# Solderable_Breadboard_Large.net
KiCad netlist of a schematic drawn in EAGLE
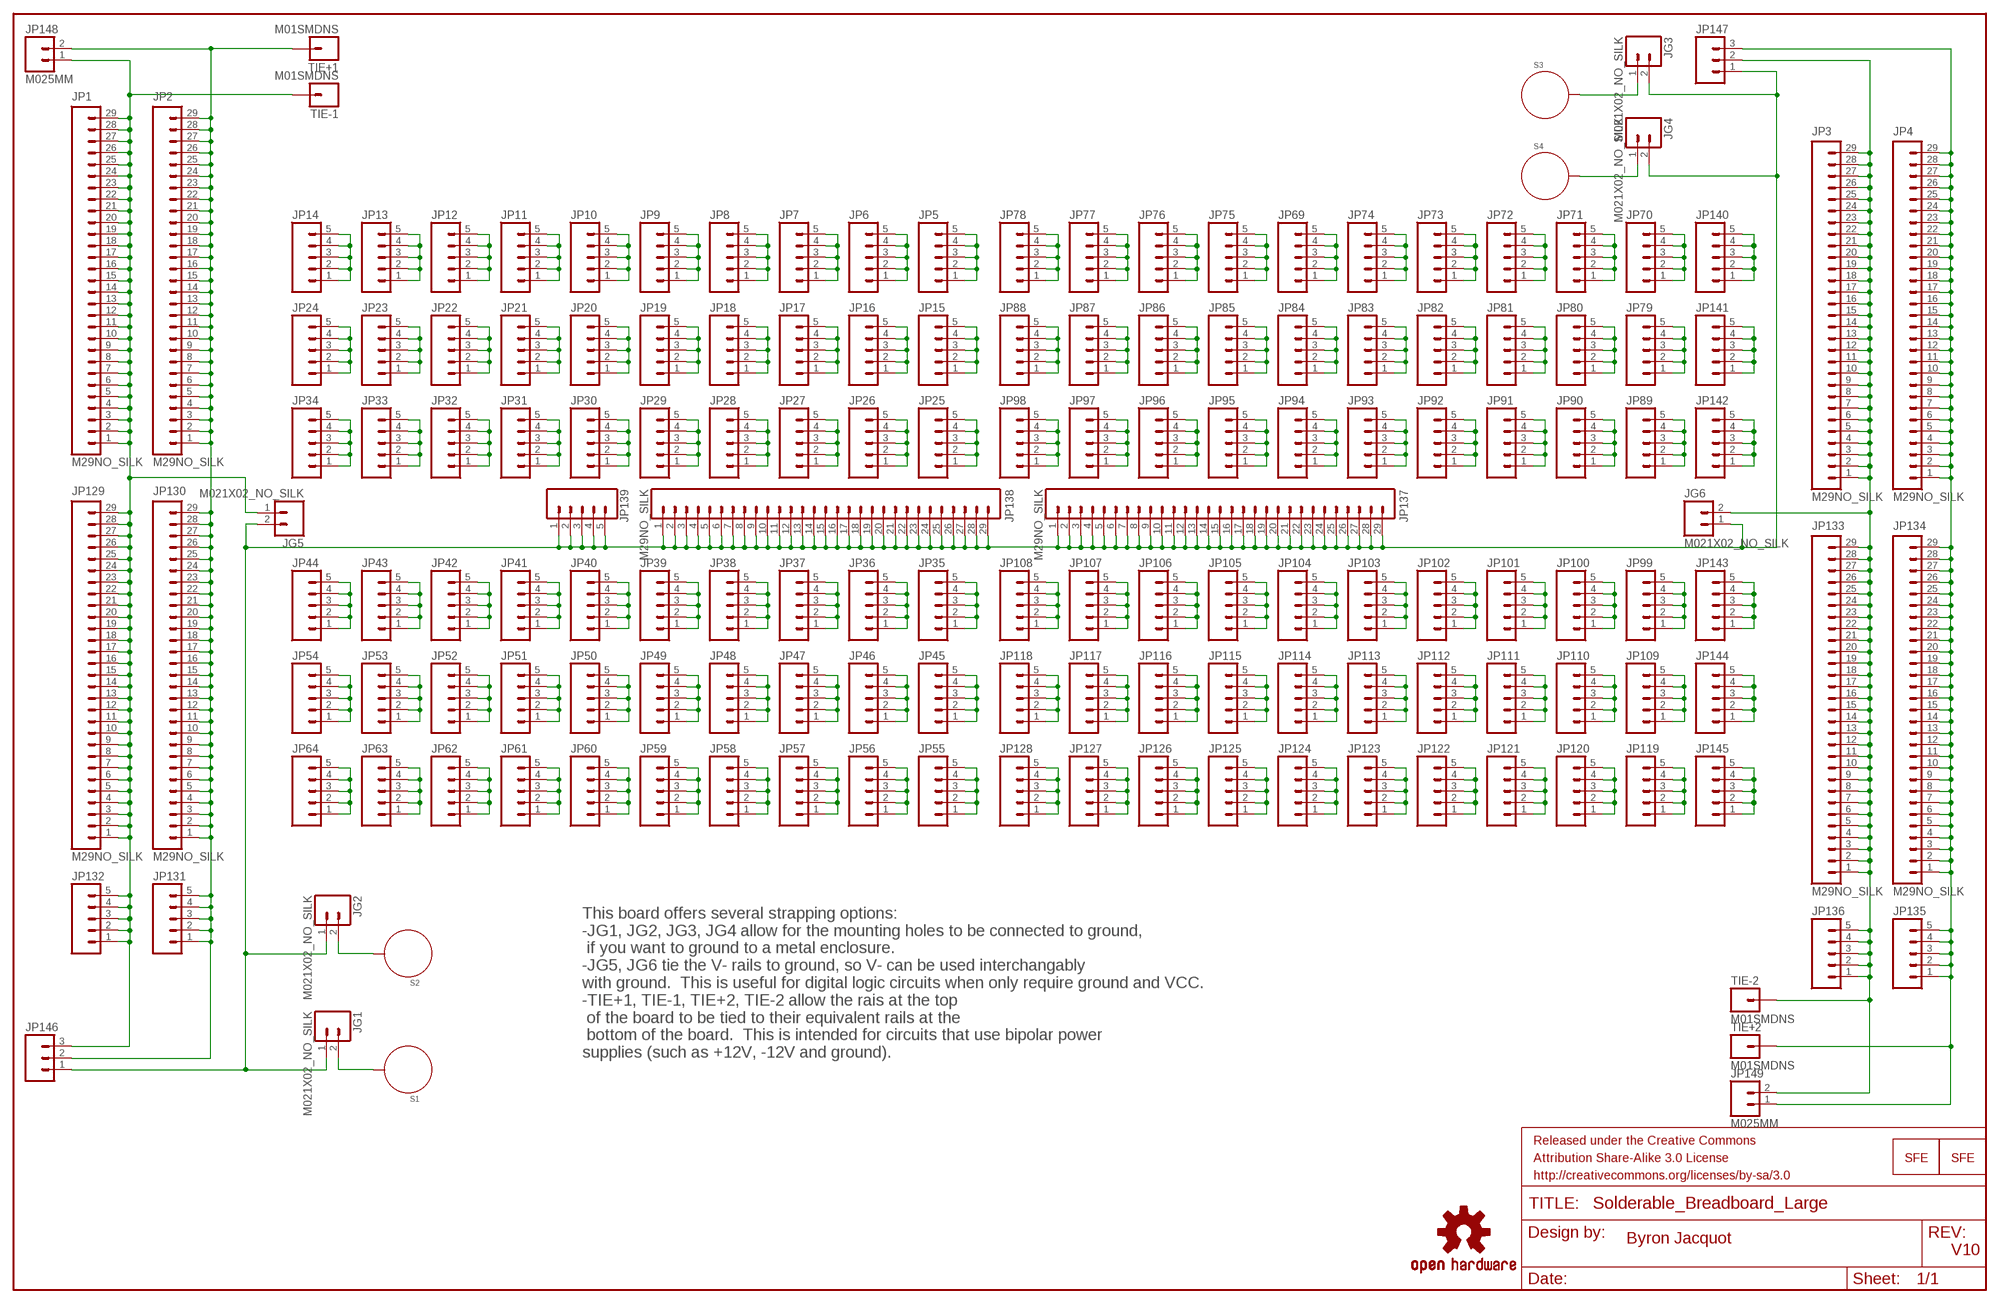
[diagram p0: schematic, sheet 1]

(export (version "E")
  (design (tool "Eeschema 10.0.6"))
  (components
    (comp (ref "FRAME2")
      (value "FRAME-LEDGER")
      (footprint "eagle-import:CREATIVE_COMMONS")
      (libsource (lib "eagle-import") (part "FRAME-LEDGER"))
    )
    (comp (ref "JG1")
      (value "M021X02_NO_SILK")
      (footprint "eagle-import:1X02_NO_SILK")
      (libsource (lib "eagle-import") (part "M021X02_NO_SILK"))
    )
    (comp (ref "JG2")
      (value "M021X02_NO_SILK")
      (footprint "eagle-import:1X02_NO_SILK")
      (libsource (lib "eagle-import") (part "M021X02_NO_SILK"))
    )
    (comp (ref "JG3")
      (value "M021X02_NO_SILK")
      (footprint "eagle-import:1X02_NO_SILK")
      (libsource (lib "eagle-import") (part "M021X02_NO_SILK"))
    )
    (comp (ref "JG4")
      (value "M021X02_NO_SILK")
      (footprint "eagle-import:1X02_NO_SILK")
      (libsource (lib "eagle-import") (part "M021X02_NO_SILK"))
    )
    (comp (ref "JG5")
      (value "M021X02_NO_SILK")
      (footprint "eagle-import:1X02_NO_SILK")
      (libsource (lib "eagle-import") (part "M021X02_NO_SILK"))
    )
    (comp (ref "JG6")
      (value "M021X02_NO_SILK")
      (footprint "eagle-import:1X02_NO_SILK")
      (libsource (lib "eagle-import") (part "M021X02_NO_SILK"))
    )
    (comp (ref "JP1")
      (value "M29NO_SILK")
      (footprint "eagle-import:1X29_NO_SILK")
      (libsource (lib "eagle-import") (part "M29NO_SILK"))
    )
    (comp (ref "JP2")
      (value "M29NO_SILK")
      (footprint "eagle-import:1X29_NO_SILK")
      (libsource (lib "eagle-import") (part "M29NO_SILK"))
    )
    (comp (ref "JP3")
      (value "M29NO_SILK")
      (footprint "eagle-import:1X29_NO_SILK")
      (libsource (lib "eagle-import") (part "M29NO_SILK"))
    )
    (comp (ref "JP4")
      (value "M29NO_SILK")
      (footprint "eagle-import:1X29_NO_SILK")
      (libsource (lib "eagle-import") (part "M29NO_SILK"))
    )
    (comp (ref "JP5")
      (value "M05NO_SILK")
      (footprint "eagle-import:1X05_NO_SILK")
      (libsource (lib "eagle-import") (part "M05NO_SILK"))
    )
    (comp (ref "JP6")
      (value "M05NO_SILK")
      (footprint "eagle-import:1X05_NO_SILK")
      (libsource (lib "eagle-import") (part "M05NO_SILK"))
    )
    (comp (ref "JP7")
      (value "M05NO_SILK")
      (footprint "eagle-import:1X05_NO_SILK")
      (libsource (lib "eagle-import") (part "M05NO_SILK"))
    )
    (comp (ref "JP8")
      (value "M05NO_SILK")
      (footprint "eagle-import:1X05_NO_SILK")
      (libsource (lib "eagle-import") (part "M05NO_SILK"))
    )
    (comp (ref "JP9")
      (value "M05NO_SILK")
      (footprint "eagle-import:1X05_NO_SILK")
      (libsource (lib "eagle-import") (part "M05NO_SILK"))
    )
    (comp (ref "JP10")
      (value "M05NO_SILK")
      (footprint "eagle-import:1X05_NO_SILK")
      (libsource (lib "eagle-import") (part "M05NO_SILK"))
    )
    (comp (ref "JP11")
      (value "M05NO_SILK")
      (footprint "eagle-import:1X05_NO_SILK")
      (libsource (lib "eagle-import") (part "M05NO_SILK"))
    )
    (comp (ref "JP12")
      (value "M05NO_SILK")
      (footprint "eagle-import:1X05_NO_SILK")
      (libsource (lib "eagle-import") (part "M05NO_SILK"))
    )
    (comp (ref "JP13")
      (value "M05NO_SILK")
      (footprint "eagle-import:1X05_NO_SILK")
      (libsource (lib "eagle-import") (part "M05NO_SILK"))
    )
    (comp (ref "JP14")
      (value "M05NO_SILK")
      (footprint "eagle-import:1X05_NO_SILK")
      (libsource (lib "eagle-import") (part "M05NO_SILK"))
    )
    (comp (ref "JP15")
      (value "M05NO_SILK")
      (footprint "eagle-import:1X05_NO_SILK")
      (libsource (lib "eagle-import") (part "M05NO_SILK"))
    )
    (comp (ref "JP16")
      (value "M05NO_SILK")
      (footprint "eagle-import:1X05_NO_SILK")
      (libsource (lib "eagle-import") (part "M05NO_SILK"))
    )
    (comp (ref "JP17")
      (value "M05NO_SILK")
      (footprint "eagle-import:1X05_NO_SILK")
      (libsource (lib "eagle-import") (part "M05NO_SILK"))
    )
    (comp (ref "JP18")
      (value "M05NO_SILK")
      (footprint "eagle-import:1X05_NO_SILK")
      (libsource (lib "eagle-import") (part "M05NO_SILK"))
    )
    (comp (ref "JP19")
      (value "M05NO_SILK")
      (footprint "eagle-import:1X05_NO_SILK")
      (libsource (lib "eagle-import") (part "M05NO_SILK"))
    )
    (comp (ref "JP20")
      (value "M05NO_SILK")
      (footprint "eagle-import:1X05_NO_SILK")
      (libsource (lib "eagle-import") (part "M05NO_SILK"))
    )
    (comp (ref "JP21")
      (value "M05NO_SILK")
      (footprint "eagle-import:1X05_NO_SILK")
      (libsource (lib "eagle-import") (part "M05NO_SILK"))
    )
    (comp (ref "JP22")
      (value "M05NO_SILK")
      (footprint "eagle-import:1X05_NO_SILK")
      (libsource (lib "eagle-import") (part "M05NO_SILK"))
    )
    (comp (ref "JP23")
      (value "M05NO_SILK")
      (footprint "eagle-import:1X05_NO_SILK")
      (libsource (lib "eagle-import") (part "M05NO_SILK"))
    )
    (comp (ref "JP24")
      (value "M05NO_SILK")
      (footprint "eagle-import:1X05_NO_SILK")
      (libsource (lib "eagle-import") (part "M05NO_SILK"))
    )
    (comp (ref "JP25")
      (value "M05NO_SILK")
      (footprint "eagle-import:1X05_NO_SILK")
      (libsource (lib "eagle-import") (part "M05NO_SILK"))
    )
    (comp (ref "JP26")
      (value "M05NO_SILK")
      (footprint "eagle-import:1X05_NO_SILK")
      (libsource (lib "eagle-import") (part "M05NO_SILK"))
    )
    (comp (ref "JP27")
      (value "M05NO_SILK")
      (footprint "eagle-import:1X05_NO_SILK")
      (libsource (lib "eagle-import") (part "M05NO_SILK"))
    )
    (comp (ref "JP28")
      (value "M05NO_SILK")
      (footprint "eagle-import:1X05_NO_SILK")
      (libsource (lib "eagle-import") (part "M05NO_SILK"))
    )
    (comp (ref "JP29")
      (value "M05NO_SILK")
      (footprint "eagle-import:1X05_NO_SILK")
      (libsource (lib "eagle-import") (part "M05NO_SILK"))
    )
    (comp (ref "JP30")
      (value "M05NO_SILK")
      (footprint "eagle-import:1X05_NO_SILK")
      (libsource (lib "eagle-import") (part "M05NO_SILK"))
    )
    (comp (ref "JP31")
      (value "M05NO_SILK")
      (footprint "eagle-import:1X05_NO_SILK")
      (libsource (lib "eagle-import") (part "M05NO_SILK"))
    )
    (comp (ref "JP32")
      (value "M05NO_SILK")
      (footprint "eagle-import:1X05_NO_SILK")
      (libsource (lib "eagle-import") (part "M05NO_SILK"))
    )
    (comp (ref "JP33")
      (value "M05NO_SILK")
      (footprint "eagle-import:1X05_NO_SILK")
      (libsource (lib "eagle-import") (part "M05NO_SILK"))
    )
    (comp (ref "JP34")
      (value "M05NO_SILK")
      (footprint "eagle-import:1X05_NO_SILK")
      (libsource (lib "eagle-import") (part "M05NO_SILK"))
    )
    (comp (ref "JP35")
      (value "M05NO_SILK")
      (footprint "eagle-import:1X05_NO_SILK")
      (libsource (lib "eagle-import") (part "M05NO_SILK"))
    )
    (comp (ref "JP36")
      (value "M05NO_SILK")
      (footprint "eagle-import:1X05_NO_SILK")
      (libsource (lib "eagle-import") (part "M05NO_SILK"))
    )
    (comp (ref "JP37")
      (value "M05NO_SILK")
      (footprint "eagle-import:1X05_NO_SILK")
      (libsource (lib "eagle-import") (part "M05NO_SILK"))
    )
    (comp (ref "JP38")
      (value "M05NO_SILK")
      (footprint "eagle-import:1X05_NO_SILK")
      (libsource (lib "eagle-import") (part "M05NO_SILK"))
    )
    (comp (ref "JP39")
      (value "M05NO_SILK")
      (footprint "eagle-import:1X05_NO_SILK")
      (libsource (lib "eagle-import") (part "M05NO_SILK"))
    )
    (comp (ref "JP40")
      (value "M05NO_SILK")
      (footprint "eagle-import:1X05_NO_SILK")
      (libsource (lib "eagle-import") (part "M05NO_SILK"))
    )
    (comp (ref "JP41")
      (value "M05NO_SILK")
      (footprint "eagle-import:1X05_NO_SILK")
      (libsource (lib "eagle-import") (part "M05NO_SILK"))
    )
    (comp (ref "JP42")
      (value "M05NO_SILK")
      (footprint "eagle-import:1X05_NO_SILK")
      (libsource (lib "eagle-import") (part "M05NO_SILK"))
    )
    (comp (ref "JP43")
      (value "M05NO_SILK")
      (footprint "eagle-import:1X05_NO_SILK")
      (libsource (lib "eagle-import") (part "M05NO_SILK"))
    )
    (comp (ref "JP44")
      (value "M05NO_SILK")
      (footprint "eagle-import:1X05_NO_SILK")
      (libsource (lib "eagle-import") (part "M05NO_SILK"))
    )
    (comp (ref "JP45")
      (value "M05NO_SILK")
      (footprint "eagle-import:1X05_NO_SILK")
      (libsource (lib "eagle-import") (part "M05NO_SILK"))
    )
    (comp (ref "JP46")
      (value "M05NO_SILK")
      (footprint "eagle-import:1X05_NO_SILK")
      (libsource (lib "eagle-import") (part "M05NO_SILK"))
    )
    (comp (ref "JP47")
      (value "M05NO_SILK")
      (footprint "eagle-import:1X05_NO_SILK")
      (libsource (lib "eagle-import") (part "M05NO_SILK"))
    )
    (comp (ref "JP48")
      (value "M05NO_SILK")
      (footprint "eagle-import:1X05_NO_SILK")
      (libsource (lib "eagle-import") (part "M05NO_SILK"))
    )
    (comp (ref "JP49")
      (value "M05NO_SILK")
      (footprint "eagle-import:1X05_NO_SILK")
      (libsource (lib "eagle-import") (part "M05NO_SILK"))
    )
    (comp (ref "JP50")
      (value "M05NO_SILK")
      (footprint "eagle-import:1X05_NO_SILK")
      (libsource (lib "eagle-import") (part "M05NO_SILK"))
    )
    (comp (ref "JP51")
      (value "M05NO_SILK")
      (footprint "eagle-import:1X05_NO_SILK")
      (libsource (lib "eagle-import") (part "M05NO_SILK"))
    )
    (comp (ref "JP52")
      (value "M05NO_SILK")
      (footprint "eagle-import:1X05_NO_SILK")
      (libsource (lib "eagle-import") (part "M05NO_SILK"))
    )
    (comp (ref "JP53")
      (value "M05NO_SILK")
      (footprint "eagle-import:1X05_NO_SILK")
      (libsource (lib "eagle-import") (part "M05NO_SILK"))
    )
    (comp (ref "JP54")
      (value "M05NO_SILK")
      (footprint "eagle-import:1X05_NO_SILK")
      (libsource (lib "eagle-import") (part "M05NO_SILK"))
    )
    (comp (ref "JP55")
      (value "M05NO_SILK")
      (footprint "eagle-import:1X05_NO_SILK")
      (libsource (lib "eagle-import") (part "M05NO_SILK"))
    )
    (comp (ref "JP56")
      (value "M05NO_SILK")
      (footprint "eagle-import:1X05_NO_SILK")
      (libsource (lib "eagle-import") (part "M05NO_SILK"))
    )
    (comp (ref "JP57")
      (value "M05NO_SILK")
      (footprint "eagle-import:1X05_NO_SILK")
      (libsource (lib "eagle-import") (part "M05NO_SILK"))
    )
    (comp (ref "JP58")
      (value "M05NO_SILK")
      (footprint "eagle-import:1X05_NO_SILK")
      (libsource (lib "eagle-import") (part "M05NO_SILK"))
    )
    (comp (ref "JP59")
      (value "M05NO_SILK")
      (footprint "eagle-import:1X05_NO_SILK")
      (libsource (lib "eagle-import") (part "M05NO_SILK"))
    )
    (comp (ref "JP60")
      (value "M05NO_SILK")
      (footprint "eagle-import:1X05_NO_SILK")
      (libsource (lib "eagle-import") (part "M05NO_SILK"))
    )
    (comp (ref "JP61")
      (value "M05NO_SILK")
      (footprint "eagle-import:1X05_NO_SILK")
      (libsource (lib "eagle-import") (part "M05NO_SILK"))
    )
    (comp (ref "JP62")
      (value "M05NO_SILK")
      (footprint "eagle-import:1X05_NO_SILK")
      (libsource (lib "eagle-import") (part "M05NO_SILK"))
    )
    (comp (ref "JP63")
      (value "M05NO_SILK")
      (footprint "eagle-import:1X05_NO_SILK")
      (libsource (lib "eagle-import") (part "M05NO_SILK"))
    )
    (comp (ref "JP64")
      (value "M05NO_SILK")
      (footprint "eagle-import:1X05_NO_SILK")
      (libsource (lib "eagle-import") (part "M05NO_SILK"))
    )
    (comp (ref "JP69")
      (value "M05NO_SILK")
      (footprint "eagle-import:1X05_NO_SILK")
      (libsource (lib "eagle-import") (part "M05NO_SILK"))
    )
    (comp (ref "JP70")
      (value "M05NO_SILK")
      (footprint "eagle-import:1X05_NO_SILK")
      (libsource (lib "eagle-import") (part "M05NO_SILK"))
    )
    (comp (ref "JP71")
      (value "M05NO_SILK")
      (footprint "eagle-import:1X05_NO_SILK")
      (libsource (lib "eagle-import") (part "M05NO_SILK"))
    )
    (comp (ref "JP72")
      (value "M05NO_SILK")
      (footprint "eagle-import:1X05_NO_SILK")
      (libsource (lib "eagle-import") (part "M05NO_SILK"))
    )
    (comp (ref "JP73")
      (value "M05NO_SILK")
      (footprint "eagle-import:1X05_NO_SILK")
      (libsource (lib "eagle-import") (part "M05NO_SILK"))
    )
    (comp (ref "JP74")
      (value "M05NO_SILK")
      (footprint "eagle-import:1X05_NO_SILK")
      (libsource (lib "eagle-import") (part "M05NO_SILK"))
    )
    (comp (ref "JP75")
      (value "M05NO_SILK")
      (footprint "eagle-import:1X05_NO_SILK")
      (libsource (lib "eagle-import") (part "M05NO_SILK"))
    )
    (comp (ref "JP76")
      (value "M05NO_SILK")
      (footprint "eagle-import:1X05_NO_SILK")
      (libsource (lib "eagle-import") (part "M05NO_SILK"))
    )
    (comp (ref "JP77")
      (value "M05NO_SILK")
      (footprint "eagle-import:1X05_NO_SILK")
      (libsource (lib "eagle-import") (part "M05NO_SILK"))
    )
    (comp (ref "JP78")
      (value "M05NO_SILK")
      (footprint "eagle-import:1X05_NO_SILK")
      (libsource (lib "eagle-import") (part "M05NO_SILK"))
    )
    (comp (ref "JP79")
      (value "M05NO_SILK")
      (footprint "eagle-import:1X05_NO_SILK")
      (libsource (lib "eagle-import") (part "M05NO_SILK"))
    )
    (comp (ref "JP80")
      (value "M05NO_SILK")
      (footprint "eagle-import:1X05_NO_SILK")
      (libsource (lib "eagle-import") (part "M05NO_SILK"))
    )
    (comp (ref "JP81")
      (value "M05NO_SILK")
      (footprint "eagle-import:1X05_NO_SILK")
      (libsource (lib "eagle-import") (part "M05NO_SILK"))
    )
    (comp (ref "JP82")
      (value "M05NO_SILK")
      (footprint "eagle-import:1X05_NO_SILK")
      (libsource (lib "eagle-import") (part "M05NO_SILK"))
    )
    (comp (ref "JP83")
      (value "M05NO_SILK")
      (footprint "eagle-import:1X05_NO_SILK")
      (libsource (lib "eagle-import") (part "M05NO_SILK"))
    )
    (comp (ref "JP84")
      (value "M05NO_SILK")
      (footprint "eagle-import:1X05_NO_SILK")
      (libsource (lib "eagle-import") (part "M05NO_SILK"))
    )
    (comp (ref "JP85")
      (value "M05NO_SILK")
      (footprint "eagle-import:1X05_NO_SILK")
      (libsource (lib "eagle-import") (part "M05NO_SILK"))
    )
    (comp (ref "JP86")
      (value "M05NO_SILK")
      (footprint "eagle-import:1X05_NO_SILK")
      (libsource (lib "eagle-import") (part "M05NO_SILK"))
    )
    (comp (ref "JP87")
      (value "M05NO_SILK")
      (footprint "eagle-import:1X05_NO_SILK")
      (libsource (lib "eagle-import") (part "M05NO_SILK"))
    )
    (comp (ref "JP88")
      (value "M05NO_SILK")
      (footprint "eagle-import:1X05_NO_SILK")
      (libsource (lib "eagle-import") (part "M05NO_SILK"))
    )
    (comp (ref "JP89")
      (value "M05NO_SILK")
      (footprint "eagle-import:1X05_NO_SILK")
      (libsource (lib "eagle-import") (part "M05NO_SILK"))
    )
    (comp (ref "JP90")
      (value "M05NO_SILK")
      (footprint "eagle-import:1X05_NO_SILK")
      (libsource (lib "eagle-import") (part "M05NO_SILK"))
    )
    (comp (ref "JP91")
      (value "M05NO_SILK")
      (footprint "eagle-import:1X05_NO_SILK")
      (libsource (lib "eagle-import") (part "M05NO_SILK"))
    )
    (comp (ref "JP92")
      (value "M05NO_SILK")
      (footprint "eagle-import:1X05_NO_SILK")
      (libsource (lib "eagle-import") (part "M05NO_SILK"))
    )
    (comp (ref "JP93")
      (value "M05NO_SILK")
      (footprint "eagle-import:1X05_NO_SILK")
      (libsource (lib "eagle-import") (part "M05NO_SILK"))
    )
    (comp (ref "JP94")
      (value "M05NO_SILK")
      (footprint "eagle-import:1X05_NO_SILK")
      (libsource (lib "eagle-import") (part "M05NO_SILK"))
    )
    (comp (ref "JP95")
      (value "M05NO_SILK")
      (footprint "eagle-import:1X05_NO_SILK")
      (libsource (lib "eagle-import") (part "M05NO_SILK"))
    )
    (comp (ref "JP96")
      (value "M05NO_SILK")
      (footprint "eagle-import:1X05_NO_SILK")
      (libsource (lib "eagle-import") (part "M05NO_SILK"))
    )
    (comp (ref "JP97")
      (value "M05NO_SILK")
      (footprint "eagle-import:1X05_NO_SILK")
      (libsource (lib "eagle-import") (part "M05NO_SILK"))
    )
    (comp (ref "JP98")
      (value "M05NO_SILK")
      (footprint "eagle-import:1X05_NO_SILK")
      (libsource (lib "eagle-import") (part "M05NO_SILK"))
    )
    (comp (ref "JP99")
      (value "M05NO_SILK")
      (footprint "eagle-import:1X05_NO_SILK")
      (libsource (lib "eagle-import") (part "M05NO_SILK"))
    )
    (comp (ref "JP100")
      (value "M05NO_SILK")
      (footprint "eagle-import:1X05_NO_SILK")
      (libsource (lib "eagle-import") (part "M05NO_SILK"))
    )
    (comp (ref "JP101")
      (value "M05NO_SILK")
      (footprint "eagle-import:1X05_NO_SILK")
      (libsource (lib "eagle-import") (part "M05NO_SILK"))
    )
    (comp (ref "JP102")
      (value "M05NO_SILK")
      (footprint "eagle-import:1X05_NO_SILK")
      (libsource (lib "eagle-import") (part "M05NO_SILK"))
    )
    (comp (ref "JP103")
      (value "M05NO_SILK")
      (footprint "eagle-import:1X05_NO_SILK")
      (libsource (lib "eagle-import") (part "M05NO_SILK"))
    )
    (comp (ref "JP104")
      (value "M05NO_SILK")
      (footprint "eagle-import:1X05_NO_SILK")
      (libsource (lib "eagle-import") (part "M05NO_SILK"))
    )
    (comp (ref "JP105")
      (value "M05NO_SILK")
      (footprint "eagle-import:1X05_NO_SILK")
      (libsource (lib "eagle-import") (part "M05NO_SILK"))
    )
    (comp (ref "JP106")
      (value "M05NO_SILK")
      (footprint "eagle-import:1X05_NO_SILK")
      (libsource (lib "eagle-import") (part "M05NO_SILK"))
    )
    (comp (ref "JP107")
      (value "M05NO_SILK")
      (footprint "eagle-import:1X05_NO_SILK")
      (libsource (lib "eagle-import") (part "M05NO_SILK"))
    )
    (comp (ref "JP108")
      (value "M05NO_SILK")
      (footprint "eagle-import:1X05_NO_SILK")
      (libsource (lib "eagle-import") (part "M05NO_SILK"))
    )
    (comp (ref "JP109")
      (value "M05NO_SILK")
      (footprint "eagle-import:1X05_NO_SILK")
      (libsource (lib "eagle-import") (part "M05NO_SILK"))
    )
    (comp (ref "JP110")
      (value "M05NO_SILK")
      (footprint "eagle-import:1X05_NO_SILK")
      (libsource (lib "eagle-import") (part "M05NO_SILK"))
    )
    (comp (ref "JP111")
      (value "M05NO_SILK")
      (footprint "eagle-import:1X05_NO_SILK")
      (libsource (lib "eagle-import") (part "M05NO_SILK"))
    )
    (comp (ref "JP112")
      (value "M05NO_SILK")
      (footprint "eagle-import:1X05_NO_SILK")
      (libsource (lib "eagle-import") (part "M05NO_SILK"))
    )
    (comp (ref "JP113")
      (value "M05NO_SILK")
      (footprint "eagle-import:1X05_NO_SILK")
      (libsource (lib "eagle-import") (part "M05NO_SILK"))
    )
    (comp (ref "JP114")
      (value "M05NO_SILK")
      (footprint "eagle-import:1X05_NO_SILK")
      (libsource (lib "eagle-import") (part "M05NO_SILK"))
    )
    (comp (ref "JP115")
      (value "M05NO_SILK")
      (footprint "eagle-import:1X05_NO_SILK")
      (libsource (lib "eagle-import") (part "M05NO_SILK"))
    )
    (comp (ref "JP116")
      (value "M05NO_SILK")
      (footprint "eagle-import:1X05_NO_SILK")
      (libsource (lib "eagle-import") (part "M05NO_SILK"))
    )
    (comp (ref "JP117")
      (value "M05NO_SILK")
      (footprint "eagle-import:1X05_NO_SILK")
      (libsource (lib "eagle-import") (part "M05NO_SILK"))
    )
    (comp (ref "JP118")
      (value "M05NO_SILK")
      (footprint "eagle-import:1X05_NO_SILK")
      (libsource (lib "eagle-import") (part "M05NO_SILK"))
    )
    (comp (ref "JP119")
      (value "M05NO_SILK")
      (footprint "eagle-import:1X05_NO_SILK")
      (libsource (lib "eagle-import") (part "M05NO_SILK"))
    )
    (comp (ref "JP120")
      (value "M05NO_SILK")
      (footprint "eagle-import:1X05_NO_SILK")
      (libsource (lib "eagle-import") (part "M05NO_SILK"))
    )
    (comp (ref "JP121")
      (value "M05NO_SILK")
      (footprint "eagle-import:1X05_NO_SILK")
      (libsource (lib "eagle-import") (part "M05NO_SILK"))
    )
    (comp (ref "JP122")
      (value "M05NO_SILK")
      (footprint "eagle-import:1X05_NO_SILK")
      (libsource (lib "eagle-import") (part "M05NO_SILK"))
    )
    (comp (ref "JP123")
      (value "M05NO_SILK")
      (footprint "eagle-import:1X05_NO_SILK")
      (libsource (lib "eagle-import") (part "M05NO_SILK"))
    )
    (comp (ref "JP124")
      (value "M05NO_SILK")
      (footprint "eagle-import:1X05_NO_SILK")
      (libsource (lib "eagle-import") (part "M05NO_SILK"))
    )
    (comp (ref "JP125")
      (value "M05NO_SILK")
      (footprint "eagle-import:1X05_NO_SILK")
      (libsource (lib "eagle-import") (part "M05NO_SILK"))
    )
    (comp (ref "JP126")
      (value "M05NO_SILK")
      (footprint "eagle-import:1X05_NO_SILK")
      (libsource (lib "eagle-import") (part "M05NO_SILK"))
    )
    (comp (ref "JP127")
      (value "M05NO_SILK")
      (footprint "eagle-import:1X05_NO_SILK")
      (libsource (lib "eagle-import") (part "M05NO_SILK"))
    )
    (comp (ref "JP128")
      (value "M05NO_SILK")
      (footprint "eagle-import:1X05_NO_SILK")
      (libsource (lib "eagle-import") (part "M05NO_SILK"))
    )
    (comp (ref "JP129")
      (value "M29NO_SILK")
      (footprint "eagle-import:1X29_NO_SILK")
      (libsource (lib "eagle-import") (part "M29NO_SILK"))
    )
    (comp (ref "JP130")
      (value "M29NO_SILK")
      (footprint "eagle-import:1X29_NO_SILK")
      (libsource (lib "eagle-import") (part "M29NO_SILK"))
    )
    (comp (ref "JP131")
      (value "M05NO_SILK")
      (footprint "eagle-import:1X05_NO_SILK")
      (libsource (lib "eagle-import") (part "M05NO_SILK"))
    )
    (comp (ref "JP132")
      (value "M05NO_SILK")
      (footprint "eagle-import:1X05_NO_SILK")
      (libsource (lib "eagle-import") (part "M05NO_SILK"))
    )
    (comp (ref "JP133")
      (value "M29NO_SILK")
      (footprint "eagle-import:1X29_NO_SILK")
      (libsource (lib "eagle-import") (part "M29NO_SILK"))
    )
    (comp (ref "JP134")
      (value "M29NO_SILK")
      (footprint "eagle-import:1X29_NO_SILK")
      (libsource (lib "eagle-import") (part "M29NO_SILK"))
    )
    (comp (ref "JP135")
      (value "M05NO_SILK")
      (footprint "eagle-import:1X05_NO_SILK")
      (libsource (lib "eagle-import") (part "M05NO_SILK"))
    )
    (comp (ref "JP136")
      (value "M05NO_SILK")
      (footprint "eagle-import:1X05_NO_SILK")
      (libsource (lib "eagle-import") (part "M05NO_SILK"))
    )
    (comp (ref "JP137")
      (value "M29NO_SILK")
      (footprint "eagle-import:1X29_NO_SILK")
      (libsource (lib "eagle-import") (part "M29NO_SILK"))
    )
    (comp (ref "JP138")
      (value "M29NO_SILK")
      (footprint "eagle-import:1X29_NO_SILK")
      (libsource (lib "eagle-import") (part "M29NO_SILK"))
    )
    (comp (ref "JP139")
      (value "M05NO_SILK")
      (footprint "eagle-import:1X05_NO_SILK")
      (libsource (lib "eagle-import") (part "M05NO_SILK"))
    )
    (comp (ref "JP140")
      (value "M05NO_SILK")
      (footprint "eagle-import:1X05_NO_SILK")
      (libsource (lib "eagle-import") (part "M05NO_SILK"))
    )
    (comp (ref "JP141")
      (value "M05NO_SILK")
      (footprint "eagle-import:1X05_NO_SILK")
      (libsource (lib "eagle-import") (part "M05NO_SILK"))
    )
    (comp (ref "JP142")
      (value "M05NO_SILK")
      (footprint "eagle-import:1X05_NO_SILK")
      (libsource (lib "eagle-import") (part "M05NO_SILK"))
    )
    (comp (ref "JP143")
      (value "M05NO_SILK")
      (footprint "eagle-import:1X05_NO_SILK")
      (libsource (lib "eagle-import") (part "M05NO_SILK"))
    )
    (comp (ref "JP144")
      (value "M05NO_SILK")
      (footprint "eagle-import:1X05_NO_SILK")
      (libsource (lib "eagle-import") (part "M05NO_SILK"))
    )
    (comp (ref "JP145")
      (value "M05NO_SILK")
      (footprint "eagle-import:1X05_NO_SILK")
      (libsource (lib "eagle-import") (part "M05NO_SILK"))
    )
    (comp (ref "JP146")
      (value "M03-SCREW-5MM")
      (footprint "eagle-import:SCREWTERMINAL-5MM-3")
      (libsource (lib "eagle-import") (part "M03-SCREW-5MM"))
    )
    (comp (ref "JP147")
      (value "M03-SCREW-5MM")
      (footprint "eagle-import:SCREWTERMINAL-5MM-3")
      (libsource (lib "eagle-import") (part "M03-SCREW-5MM"))
    )
    (comp (ref "JP148")
      (value "M025MM")
      (footprint "eagle-import:SCREWTERMINAL-5MM-2")
      (libsource (lib "eagle-import") (part "M025MM"))
    )
    (comp (ref "JP149")
      (value "M025MM")
      (footprint "eagle-import:SCREWTERMINAL-5MM-2")
      (libsource (lib "eagle-import") (part "M025MM"))
    )
    (comp (ref "LOGO1")
      (value "LOGO-SFENEW")
      (footprint "eagle-import:SFE-NEW-WEBLOGO")
      (libsource (lib "eagle-import") (part "LOGO-SFENEW"))
    )
    (comp (ref "LOGO2")
      (value "LOGO-SFENEW")
      (footprint "eagle-import:SFE-NEW-WEBLOGO")
      (libsource (lib "eagle-import") (part "LOGO-SFENEW"))
    )
    (comp (ref "LOGO3")
      (value "OSHW-LOGOS")
      (footprint "eagle-import:OSHW-LOGO-S")
      (libsource (lib "eagle-import") (part "OSHW-LOGOS"))
    )
    (comp (ref "S1")
      (value "STANDOFF_ELECTRICAL")
      (footprint "eagle-import:STANDOFF-ELECTRICAL")
      (libsource (lib "eagle-import") (part "STANDOFF_ELECTRICAL"))
    )
    (comp (ref "S2")
      (value "STANDOFF_ELECTRICAL")
      (footprint "eagle-import:STANDOFF-ELECTRICAL")
      (libsource (lib "eagle-import") (part "STANDOFF_ELECTRICAL"))
    )
    (comp (ref "S3")
      (value "STANDOFF_ELECTRICAL")
      (footprint "eagle-import:STANDOFF-ELECTRICAL")
      (libsource (lib "eagle-import") (part "STANDOFF_ELECTRICAL"))
    )
    (comp (ref "S4")
      (value "STANDOFF_ELECTRICAL")
      (footprint "eagle-import:STANDOFF-ELECTRICAL")
      (libsource (lib "eagle-import") (part "STANDOFF_ELECTRICAL"))
    )
    (comp (ref "TIE+1")
      (value "M01SMDNS")
      (footprint "eagle-import:1X01NS")
      (libsource (lib "eagle-import") (part "M01SMDNS"))
    )
    (comp (ref "TIE+2")
      (value "M01SMDNS")
      (footprint "eagle-import:1X01NS")
      (libsource (lib "eagle-import") (part "M01SMDNS"))
    )
    (comp (ref "TIE-1")
      (value "M01SMDNS")
      (footprint "eagle-import:1X01NS")
      (libsource (lib "eagle-import") (part "M01SMDNS"))
    )
    (comp (ref "TIE-2")
      (value "M01SMDNS")
      (footprint "eagle-import:1X01NS")
      (libsource (lib "eagle-import") (part "M01SMDNS"))
    )
  )
  (nets
    (net (code "1") (name "Net-(JG1-Pad1)") (class "Default")
      (node (ref "JG1") (pin "1") (pinfunction "1_1") (pintype "passive"))
      (node (ref "JG2") (pin "1") (pinfunction "1_1") (pintype "passive"))
      (node (ref "JG3") (pin "2") (pinfunction "2_2") (pintype "passive"))
      (node (ref "JG4") (pin "2") (pinfunction "2_2") (pintype "passive"))
      (node (ref "JG5") (pin "2") (pinfunction "2_2") (pintype "passive"))
      (node (ref "JG6") (pin "1") (pinfunction "1_1") (pintype "passive"))
      (node (ref "JP137") (pin "1") (pinfunction "1_1") (pintype "passive"))
      (node (ref "JP137") (pin "10") (pinfunction "10_10") (pintype "passive"))
      (node (ref "JP137") (pin "11") (pinfunction "11_11") (pintype "passive"))
      (node (ref "JP137") (pin "12") (pinfunction "12_12") (pintype "passive"))
      (node (ref "JP137") (pin "13") (pinfunction "13_13") (pintype "passive"))
      (node (ref "JP137") (pin "14") (pinfunction "14_14") (pintype "passive"))
      (node (ref "JP137") (pin "15") (pinfunction "15_15") (pintype "passive"))
      (node (ref "JP137") (pin "16") (pinfunction "16_16") (pintype "passive"))
      (node (ref "JP137") (pin "17") (pinfunction "17_17") (pintype "passive"))
      (node (ref "JP137") (pin "18") (pinfunction "18_18") (pintype "passive"))
      (node (ref "JP137") (pin "19") (pinfunction "19_19") (pintype "passive"))
      (node (ref "JP137") (pin "2") (pinfunction "2_2") (pintype "passive"))
      (node (ref "JP137") (pin "20") (pinfunction "20_20") (pintype "passive"))
      (node (ref "JP137") (pin "21") (pinfunction "21_21") (pintype "passive"))
      (node (ref "JP137") (pin "22") (pinfunction "22_22") (pintype "passive"))
      (node (ref "JP137") (pin "23") (pinfunction "23_23") (pintype "passive"))
      (node (ref "JP137") (pin "24") (pinfunction "24_24") (pintype "passive"))
      (node (ref "JP137") (pin "25") (pinfunction "25_25") (pintype "passive"))
      (node (ref "JP137") (pin "26") (pinfunction "26_26") (pintype "passive"))
      (node (ref "JP137") (pin "27") (pinfunction "27_27") (pintype "passive"))
      (node (ref "JP137") (pin "28") (pinfunction "28_28") (pintype "passive"))
      (node (ref "JP137") (pin "29") (pinfunction "29_29") (pintype "passive"))
      (node (ref "JP137") (pin "3") (pinfunction "3_3") (pintype "passive"))
      (node (ref "JP137") (pin "4") (pinfunction "4_4") (pintype "passive"))
      (node (ref "JP137") (pin "5") (pinfunction "5_5") (pintype "passive"))
      (node (ref "JP137") (pin "6") (pinfunction "6_6") (pintype "passive"))
      (node (ref "JP137") (pin "7") (pinfunction "7_7") (pintype "passive"))
      (node (ref "JP137") (pin "8") (pinfunction "8_8") (pintype "passive"))
      (node (ref "JP137") (pin "9") (pinfunction "9_9") (pintype "passive"))
      (node (ref "JP138") (pin "1") (pinfunction "1_1") (pintype "passive"))
      (node (ref "JP138") (pin "10") (pinfunction "10_10") (pintype "passive"))
      (node (ref "JP138") (pin "11") (pinfunction "11_11") (pintype "passive"))
      (node (ref "JP138") (pin "12") (pinfunction "12_12") (pintype "passive"))
      (node (ref "JP138") (pin "13") (pinfunction "13_13") (pintype "passive"))
      (node (ref "JP138") (pin "14") (pinfunction "14_14") (pintype "passive"))
      (node (ref "JP138") (pin "15") (pinfunction "15_15") (pintype "passive"))
      (node (ref "JP138") (pin "16") (pinfunction "16_16") (pintype "passive"))
      (node (ref "JP138") (pin "17") (pinfunction "17_17") (pintype "passive"))
      (node (ref "JP138") (pin "18") (pinfunction "18_18") (pintype "passive"))
      (node (ref "JP138") (pin "19") (pinfunction "19_19") (pintype "passive"))
      (node (ref "JP138") (pin "2") (pinfunction "2_2") (pintype "passive"))
      (node (ref "JP138") (pin "20") (pinfunction "20_20") (pintype "passive"))
      (node (ref "JP138") (pin "21") (pinfunction "21_21") (pintype "passive"))
      (node (ref "JP138") (pin "22") (pinfunction "22_22") (pintype "passive"))
      (node (ref "JP138") (pin "23") (pinfunction "23_23") (pintype "passive"))
      (node (ref "JP138") (pin "24") (pinfunction "24_24") (pintype "passive"))
      (node (ref "JP138") (pin "25") (pinfunction "25_25") (pintype "passive"))
      (node (ref "JP138") (pin "26") (pinfunction "26_26") (pintype "passive"))
      (node (ref "JP138") (pin "27") (pinfunction "27_27") (pintype "passive"))
      (node (ref "JP138") (pin "28") (pinfunction "28_28") (pintype "passive"))
      (node (ref "JP138") (pin "29") (pinfunction "29_29") (pintype "passive"))
      (node (ref "JP138") (pin "3") (pinfunction "3_3") (pintype "passive"))
      (node (ref "JP138") (pin "4") (pinfunction "4_4") (pintype "passive"))
      (node (ref "JP138") (pin "5") (pinfunction "5_5") (pintype "passive"))
      (node (ref "JP138") (pin "6") (pinfunction "6_6") (pintype "passive"))
      (node (ref "JP138") (pin "7") (pinfunction "7_7") (pintype "passive"))
      (node (ref "JP138") (pin "8") (pinfunction "8_8") (pintype "passive"))
      (node (ref "JP138") (pin "9") (pinfunction "9_9") (pintype "passive"))
      (node (ref "JP139") (pin "1") (pinfunction "1_1") (pintype "passive"))
      (node (ref "JP139") (pin "2") (pinfunction "2_2") (pintype "passive"))
      (node (ref "JP139") (pin "3") (pinfunction "3_3") (pintype "passive"))
      (node (ref "JP139") (pin "4") (pinfunction "4_4") (pintype "passive"))
      (node (ref "JP139") (pin "5") (pinfunction "5_5") (pintype "passive"))
      (node (ref "JP146") (pin "1") (pinfunction "1_1") (pintype "passive"))
      (node (ref "JP147") (pin "1") (pinfunction "1_1") (pintype "passive"))
    )
    (net (code "2") (name "Net-(JG5-Pad1)") (class "Default")
      (node (ref "JG5") (pin "1") (pinfunction "1_1") (pintype "passive"))
      (node (ref "JP1") (pin "1") (pinfunction "1_1") (pintype "passive"))
      (node (ref "JP1") (pin "10") (pinfunction "10_10") (pintype "passive"))
      (node (ref "JP1") (pin "11") (pinfunction "11_11") (pintype "passive"))
      (node (ref "JP1") (pin "12") (pinfunction "12_12") (pintype "passive"))
      (node (ref "JP1") (pin "13") (pinfunction "13_13") (pintype "passive"))
      (node (ref "JP1") (pin "14") (pinfunction "14_14") (pintype "passive"))
      (node (ref "JP1") (pin "15") (pinfunction "15_15") (pintype "passive"))
      (node (ref "JP1") (pin "16") (pinfunction "16_16") (pintype "passive"))
      (node (ref "JP1") (pin "17") (pinfunction "17_17") (pintype "passive"))
      (node (ref "JP1") (pin "18") (pinfunction "18_18") (pintype "passive"))
      (node (ref "JP1") (pin "19") (pinfunction "19_19") (pintype "passive"))
      (node (ref "JP1") (pin "2") (pinfunction "2_2") (pintype "passive"))
      (node (ref "JP1") (pin "20") (pinfunction "20_20") (pintype "passive"))
      (node (ref "JP1") (pin "21") (pinfunction "21_21") (pintype "passive"))
      (node (ref "JP1") (pin "22") (pinfunction "22_22") (pintype "passive"))
      (node (ref "JP1") (pin "23") (pinfunction "23_23") (pintype "passive"))
      (node (ref "JP1") (pin "24") (pinfunction "24_24") (pintype "passive"))
      (node (ref "JP1") (pin "25") (pinfunction "25_25") (pintype "passive"))
      (node (ref "JP1") (pin "26") (pinfunction "26_26") (pintype "passive"))
      (node (ref "JP1") (pin "27") (pinfunction "27_27") (pintype "passive"))
      (node (ref "JP1") (pin "28") (pinfunction "28_28") (pintype "passive"))
      (node (ref "JP1") (pin "29") (pinfunction "29_29") (pintype "passive"))
      (node (ref "JP1") (pin "3") (pinfunction "3_3") (pintype "passive"))
      (node (ref "JP1") (pin "4") (pinfunction "4_4") (pintype "passive"))
      (node (ref "JP1") (pin "5") (pinfunction "5_5") (pintype "passive"))
      (node (ref "JP1") (pin "6") (pinfunction "6_6") (pintype "passive"))
      (node (ref "JP1") (pin "7") (pinfunction "7_7") (pintype "passive"))
      (node (ref "JP1") (pin "8") (pinfunction "8_8") (pintype "passive"))
      (node (ref "JP1") (pin "9") (pinfunction "9_9") (pintype "passive"))
      (node (ref "JP129") (pin "1") (pinfunction "1_1") (pintype "passive"))
      (node (ref "JP129") (pin "10") (pinfunction "10_10") (pintype "passive"))
      (node (ref "JP129") (pin "11") (pinfunction "11_11") (pintype "passive"))
      (node (ref "JP129") (pin "12") (pinfunction "12_12") (pintype "passive"))
      (node (ref "JP129") (pin "13") (pinfunction "13_13") (pintype "passive"))
      (node (ref "JP129") (pin "14") (pinfunction "14_14") (pintype "passive"))
      (node (ref "JP129") (pin "15") (pinfunction "15_15") (pintype "passive"))
      (node (ref "JP129") (pin "16") (pinfunction "16_16") (pintype "passive"))
      (node (ref "JP129") (pin "17") (pinfunction "17_17") (pintype "passive"))
      (node (ref "JP129") (pin "18") (pinfunction "18_18") (pintype "passive"))
      (node (ref "JP129") (pin "19") (pinfunction "19_19") (pintype "passive"))
      (node (ref "JP129") (pin "2") (pinfunction "2_2") (pintype "passive"))
      (node (ref "JP129") (pin "20") (pinfunction "20_20") (pintype "passive"))
      (node (ref "JP129") (pin "21") (pinfunction "21_21") (pintype "passive"))
      (node (ref "JP129") (pin "22") (pinfunction "22_22") (pintype "passive"))
      (node (ref "JP129") (pin "23") (pinfunction "23_23") (pintype "passive"))
      (node (ref "JP129") (pin "24") (pinfunction "24_24") (pintype "passive"))
      (node (ref "JP129") (pin "25") (pinfunction "25_25") (pintype "passive"))
      (node (ref "JP129") (pin "26") (pinfunction "26_26") (pintype "passive"))
      (node (ref "JP129") (pin "27") (pinfunction "27_27") (pintype "passive"))
      (node (ref "JP129") (pin "28") (pinfunction "28_28") (pintype "passive"))
      (node (ref "JP129") (pin "29") (pinfunction "29_29") (pintype "passive"))
      (node (ref "JP129") (pin "3") (pinfunction "3_3") (pintype "passive"))
      (node (ref "JP129") (pin "4") (pinfunction "4_4") (pintype "passive"))
      (node (ref "JP129") (pin "5") (pinfunction "5_5") (pintype "passive"))
      (node (ref "JP129") (pin "6") (pinfunction "6_6") (pintype "passive"))
      (node (ref "JP129") (pin "7") (pinfunction "7_7") (pintype "passive"))
      (node (ref "JP129") (pin "8") (pinfunction "8_8") (pintype "passive"))
      (node (ref "JP129") (pin "9") (pinfunction "9_9") (pintype "passive"))
      (node (ref "JP132") (pin "1") (pinfunction "1_1") (pintype "passive"))
      (node (ref "JP132") (pin "2") (pinfunction "2_2") (pintype "passive"))
      (node (ref "JP132") (pin "3") (pinfunction "3_3") (pintype "passive"))
      (node (ref "JP132") (pin "4") (pinfunction "4_4") (pintype "passive"))
      (node (ref "JP132") (pin "5") (pinfunction "5_5") (pintype "passive"))
      (node (ref "JP146") (pin "3") (pinfunction "3_3") (pintype "passive"))
      (node (ref "JP148") (pin "1") (pinfunction "1_1") (pintype "passive"))
      (node (ref "TIE-1") (pin "1") (pinfunction "1_1") (pintype "passive"))
    )
    (net (code "3") (name "Net-(JG6-Pad2)") (class "Default")
      (node (ref "JG6") (pin "2") (pinfunction "2_2") (pintype "passive"))
      (node (ref "JP133") (pin "1") (pinfunction "1_1") (pintype "passive"))
      (node (ref "JP133") (pin "10") (pinfunction "10_10") (pintype "passive"))
      (node (ref "JP133") (pin "11") (pinfunction "11_11") (pintype "passive"))
      (node (ref "JP133") (pin "12") (pinfunction "12_12") (pintype "passive"))
      (node (ref "JP133") (pin "13") (pinfunction "13_13") (pintype "passive"))
      (node (ref "JP133") (pin "14") (pinfunction "14_14") (pintype "passive"))
      (node (ref "JP133") (pin "15") (pinfunction "15_15") (pintype "passive"))
      (node (ref "JP133") (pin "16") (pinfunction "16_16") (pintype "passive"))
      (node (ref "JP133") (pin "17") (pinfunction "17_17") (pintype "passive"))
      (node (ref "JP133") (pin "18") (pinfunction "18_18") (pintype "passive"))
      (node (ref "JP133") (pin "19") (pinfunction "19_19") (pintype "passive"))
      (node (ref "JP133") (pin "2") (pinfunction "2_2") (pintype "passive"))
      (node (ref "JP133") (pin "20") (pinfunction "20_20") (pintype "passive"))
      (node (ref "JP133") (pin "21") (pinfunction "21_21") (pintype "passive"))
      (node (ref "JP133") (pin "22") (pinfunction "22_22") (pintype "passive"))
      (node (ref "JP133") (pin "23") (pinfunction "23_23") (pintype "passive"))
      (node (ref "JP133") (pin "24") (pinfunction "24_24") (pintype "passive"))
      (node (ref "JP133") (pin "25") (pinfunction "25_25") (pintype "passive"))
      (node (ref "JP133") (pin "26") (pinfunction "26_26") (pintype "passive"))
      (node (ref "JP133") (pin "27") (pinfunction "27_27") (pintype "passive"))
      (node (ref "JP133") (pin "28") (pinfunction "28_28") (pintype "passive"))
      (node (ref "JP133") (pin "29") (pinfunction "29_29") (pintype "passive"))
      (node (ref "JP133") (pin "3") (pinfunction "3_3") (pintype "passive"))
      (node (ref "JP133") (pin "4") (pinfunction "4_4") (pintype "passive"))
      (node (ref "JP133") (pin "5") (pinfunction "5_5") (pintype "passive"))
      (node (ref "JP133") (pin "6") (pinfunction "6_6") (pintype "passive"))
      (node (ref "JP133") (pin "7") (pinfunction "7_7") (pintype "passive"))
      (node (ref "JP133") (pin "8") (pinfunction "8_8") (pintype "passive"))
      (node (ref "JP133") (pin "9") (pinfunction "9_9") (pintype "passive"))
      (node (ref "JP136") (pin "1") (pinfunction "1_1") (pintype "passive"))
      (node (ref "JP136") (pin "2") (pinfunction "2_2") (pintype "passive"))
      (node (ref "JP136") (pin "3") (pinfunction "3_3") (pintype "passive"))
      (node (ref "JP136") (pin "4") (pinfunction "4_4") (pintype "passive"))
      (node (ref "JP136") (pin "5") (pinfunction "5_5") (pintype "passive"))
      (node (ref "JP147") (pin "2") (pinfunction "2_2") (pintype "passive"))
      (node (ref "JP149") (pin "2") (pinfunction "2_2") (pintype "passive"))
      (node (ref "JP3") (pin "1") (pinfunction "1_1") (pintype "passive"))
      (node (ref "JP3") (pin "10") (pinfunction "10_10") (pintype "passive"))
      (node (ref "JP3") (pin "11") (pinfunction "11_11") (pintype "passive"))
      (node (ref "JP3") (pin "12") (pinfunction "12_12") (pintype "passive"))
      (node (ref "JP3") (pin "13") (pinfunction "13_13") (pintype "passive"))
      (node (ref "JP3") (pin "14") (pinfunction "14_14") (pintype "passive"))
      (node (ref "JP3") (pin "15") (pinfunction "15_15") (pintype "passive"))
      (node (ref "JP3") (pin "16") (pinfunction "16_16") (pintype "passive"))
      (node (ref "JP3") (pin "17") (pinfunction "17_17") (pintype "passive"))
      (node (ref "JP3") (pin "18") (pinfunction "18_18") (pintype "passive"))
      (node (ref "JP3") (pin "19") (pinfunction "19_19") (pintype "passive"))
      (node (ref "JP3") (pin "2") (pinfunction "2_2") (pintype "passive"))
      (node (ref "JP3") (pin "20") (pinfunction "20_20") (pintype "passive"))
      (node (ref "JP3") (pin "21") (pinfunction "21_21") (pintype "passive"))
      (node (ref "JP3") (pin "22") (pinfunction "22_22") (pintype "passive"))
      (node (ref "JP3") (pin "23") (pinfunction "23_23") (pintype "passive"))
      (node (ref "JP3") (pin "24") (pinfunction "24_24") (pintype "passive"))
      (node (ref "JP3") (pin "25") (pinfunction "25_25") (pintype "passive"))
      (node (ref "JP3") (pin "26") (pinfunction "26_26") (pintype "passive"))
      (node (ref "JP3") (pin "27") (pinfunction "27_27") (pintype "passive"))
      (node (ref "JP3") (pin "28") (pinfunction "28_28") (pintype "passive"))
      (node (ref "JP3") (pin "29") (pinfunction "29_29") (pintype "passive"))
      (node (ref "JP3") (pin "3") (pinfunction "3_3") (pintype "passive"))
      (node (ref "JP3") (pin "4") (pinfunction "4_4") (pintype "passive"))
      (node (ref "JP3") (pin "5") (pinfunction "5_5") (pintype "passive"))
      (node (ref "JP3") (pin "6") (pinfunction "6_6") (pintype "passive"))
      (node (ref "JP3") (pin "7") (pinfunction "7_7") (pintype "passive"))
      (node (ref "JP3") (pin "8") (pinfunction "8_8") (pintype "passive"))
      (node (ref "JP3") (pin "9") (pinfunction "9_9") (pintype "passive"))
      (node (ref "TIE-2") (pin "1") (pinfunction "1_1") (pintype "passive"))
    )
    (net (code "4") (name "Net-(JP5-Pad1)") (class "Default")
      (node (ref "JP5") (pin "1") (pinfunction "1_1") (pintype "passive"))
      (node (ref "JP5") (pin "2") (pinfunction "2_2") (pintype "passive"))
      (node (ref "JP5") (pin "3") (pinfunction "3_3") (pintype "passive"))
      (node (ref "JP5") (pin "4") (pinfunction "4_4") (pintype "passive"))
      (node (ref "JP5") (pin "5") (pinfunction "5_5") (pintype "passive"))
    )
    (net (code "5") (name "Net-(JP6-Pad1)") (class "Default")
      (node (ref "JP6") (pin "1") (pinfunction "1_1") (pintype "passive"))
      (node (ref "JP6") (pin "2") (pinfunction "2_2") (pintype "passive"))
      (node (ref "JP6") (pin "3") (pinfunction "3_3") (pintype "passive"))
      (node (ref "JP6") (pin "4") (pinfunction "4_4") (pintype "passive"))
      (node (ref "JP6") (pin "5") (pinfunction "5_5") (pintype "passive"))
    )
    (net (code "6") (name "Net-(JP7-Pad1)") (class "Default")
      (node (ref "JP7") (pin "1") (pinfunction "1_1") (pintype "passive"))
      (node (ref "JP7") (pin "2") (pinfunction "2_2") (pintype "passive"))
      (node (ref "JP7") (pin "3") (pinfunction "3_3") (pintype "passive"))
      (node (ref "JP7") (pin "4") (pinfunction "4_4") (pintype "passive"))
      (node (ref "JP7") (pin "5") (pinfunction "5_5") (pintype "passive"))
    )
    (net (code "7") (name "Net-(JP8-Pad1)") (class "Default")
      (node (ref "JP8") (pin "1") (pinfunction "1_1") (pintype "passive"))
      (node (ref "JP8") (pin "2") (pinfunction "2_2") (pintype "passive"))
      (node (ref "JP8") (pin "3") (pinfunction "3_3") (pintype "passive"))
      (node (ref "JP8") (pin "4") (pinfunction "4_4") (pintype "passive"))
      (node (ref "JP8") (pin "5") (pinfunction "5_5") (pintype "passive"))
    )
    (net (code "8") (name "Net-(JP9-Pad1)") (class "Default")
      (node (ref "JP9") (pin "1") (pinfunction "1_1") (pintype "passive"))
      (node (ref "JP9") (pin "2") (pinfunction "2_2") (pintype "passive"))
      (node (ref "JP9") (pin "3") (pinfunction "3_3") (pintype "passive"))
      (node (ref "JP9") (pin "4") (pinfunction "4_4") (pintype "passive"))
      (node (ref "JP9") (pin "5") (pinfunction "5_5") (pintype "passive"))
    )
    (net (code "9") (name "Net-(JP10-Pad1)") (class "Default")
      (node (ref "JP10") (pin "1") (pinfunction "1_1") (pintype "passive"))
      (node (ref "JP10") (pin "2") (pinfunction "2_2") (pintype "passive"))
      (node (ref "JP10") (pin "3") (pinfunction "3_3") (pintype "passive"))
      (node (ref "JP10") (pin "4") (pinfunction "4_4") (pintype "passive"))
      (node (ref "JP10") (pin "5") (pinfunction "5_5") (pintype "passive"))
    )
    (net (code "10") (name "Net-(JP11-Pad1)") (class "Default")
      (node (ref "JP11") (pin "1") (pinfunction "1_1") (pintype "passive"))
      (node (ref "JP11") (pin "2") (pinfunction "2_2") (pintype "passive"))
      (node (ref "JP11") (pin "3") (pinfunction "3_3") (pintype "passive"))
      (node (ref "JP11") (pin "4") (pinfunction "4_4") (pintype "passive"))
      (node (ref "JP11") (pin "5") (pinfunction "5_5") (pintype "passive"))
    )
    (net (code "11") (name "Net-(JP12-Pad1)") (class "Default")
      (node (ref "JP12") (pin "1") (pinfunction "1_1") (pintype "passive"))
      (node (ref "JP12") (pin "2") (pinfunction "2_2") (pintype "passive"))
      (node (ref "JP12") (pin "3") (pinfunction "3_3") (pintype "passive"))
      (node (ref "JP12") (pin "4") (pinfunction "4_4") (pintype "passive"))
      (node (ref "JP12") (pin "5") (pinfunction "5_5") (pintype "passive"))
    )
    (net (code "12") (name "Net-(JP13-Pad1)") (class "Default")
      (node (ref "JP13") (pin "1") (pinfunction "1_1") (pintype "passive"))
      (node (ref "JP13") (pin "2") (pinfunction "2_2") (pintype "passive"))
      (node (ref "JP13") (pin "3") (pinfunction "3_3") (pintype "passive"))
      (node (ref "JP13") (pin "4") (pinfunction "4_4") (pintype "passive"))
      (node (ref "JP13") (pin "5") (pinfunction "5_5") (pintype "passive"))
    )
    (net (code "13") (name "Net-(JP14-Pad1)") (class "Default")
      (node (ref "JP14") (pin "1") (pinfunction "1_1") (pintype "passive"))
      (node (ref "JP14") (pin "2") (pinfunction "2_2") (pintype "passive"))
      (node (ref "JP14") (pin "3") (pinfunction "3_3") (pintype "passive"))
      (node (ref "JP14") (pin "4") (pinfunction "4_4") (pintype "passive"))
      (node (ref "JP14") (pin "5") (pinfunction "5_5") (pintype "passive"))
    )
    (net (code "14") (name "Net-(JP15-Pad1)") (class "Default")
      (node (ref "JP15") (pin "1") (pinfunction "1_1") (pintype "passive"))
      (node (ref "JP15") (pin "2") (pinfunction "2_2") (pintype "passive"))
      (node (ref "JP15") (pin "3") (pinfunction "3_3") (pintype "passive"))
      (node (ref "JP15") (pin "4") (pinfunction "4_4") (pintype "passive"))
      (node (ref "JP15") (pin "5") (pinfunction "5_5") (pintype "passive"))
    )
    (net (code "15") (name "Net-(JP16-Pad1)") (class "Default")
      (node (ref "JP16") (pin "1") (pinfunction "1_1") (pintype "passive"))
      (node (ref "JP16") (pin "2") (pinfunction "2_2") (pintype "passive"))
      (node (ref "JP16") (pin "3") (pinfunction "3_3") (pintype "passive"))
      (node (ref "JP16") (pin "4") (pinfunction "4_4") (pintype "passive"))
      (node (ref "JP16") (pin "5") (pinfunction "5_5") (pintype "passive"))
    )
    (net (code "16") (name "Net-(JP17-Pad1)") (class "Default")
      (node (ref "JP17") (pin "1") (pinfunction "1_1") (pintype "passive"))
      (node (ref "JP17") (pin "2") (pinfunction "2_2") (pintype "passive"))
      (node (ref "JP17") (pin "3") (pinfunction "3_3") (pintype "passive"))
      (node (ref "JP17") (pin "4") (pinfunction "4_4") (pintype "passive"))
      (node (ref "JP17") (pin "5") (pinfunction "5_5") (pintype "passive"))
    )
    (net (code "17") (name "Net-(JP18-Pad1)") (class "Default")
      (node (ref "JP18") (pin "1") (pinfunction "1_1") (pintype "passive"))
      (node (ref "JP18") (pin "2") (pinfunction "2_2") (pintype "passive"))
      (node (ref "JP18") (pin "3") (pinfunction "3_3") (pintype "passive"))
      (node (ref "JP18") (pin "4") (pinfunction "4_4") (pintype "passive"))
      (node (ref "JP18") (pin "5") (pinfunction "5_5") (pintype "passive"))
    )
    (net (code "18") (name "Net-(JP19-Pad1)") (class "Default")
      (node (ref "JP19") (pin "1") (pinfunction "1_1") (pintype "passive"))
      (node (ref "JP19") (pin "2") (pinfunction "2_2") (pintype "passive"))
      (node (ref "JP19") (pin "3") (pinfunction "3_3") (pintype "passive"))
      (node (ref "JP19") (pin "4") (pinfunction "4_4") (pintype "passive"))
      (node (ref "JP19") (pin "5") (pinfunction "5_5") (pintype "passive"))
    )
    (net (code "19") (name "Net-(JP20-Pad1)") (class "Default")
      (node (ref "JP20") (pin "1") (pinfunction "1_1") (pintype "passive"))
      (node (ref "JP20") (pin "2") (pinfunction "2_2") (pintype "passive"))
      (node (ref "JP20") (pin "3") (pinfunction "3_3") (pintype "passive"))
      (node (ref "JP20") (pin "4") (pinfunction "4_4") (pintype "passive"))
      (node (ref "JP20") (pin "5") (pinfunction "5_5") (pintype "passive"))
    )
    (net (code "20") (name "Net-(JP21-Pad1)") (class "Default")
      (node (ref "JP21") (pin "1") (pinfunction "1_1") (pintype "passive"))
      (node (ref "JP21") (pin "2") (pinfunction "2_2") (pintype "passive"))
      (node (ref "JP21") (pin "3") (pinfunction "3_3") (pintype "passive"))
      (node (ref "JP21") (pin "4") (pinfunction "4_4") (pintype "passive"))
      (node (ref "JP21") (pin "5") (pinfunction "5_5") (pintype "passive"))
    )
    (net (code "21") (name "Net-(JP22-Pad1)") (class "Default")
      (node (ref "JP22") (pin "1") (pinfunction "1_1") (pintype "passive"))
      (node (ref "JP22") (pin "2") (pinfunction "2_2") (pintype "passive"))
      (node (ref "JP22") (pin "3") (pinfunction "3_3") (pintype "passive"))
      (node (ref "JP22") (pin "4") (pinfunction "4_4") (pintype "passive"))
      (node (ref "JP22") (pin "5") (pinfunction "5_5") (pintype "passive"))
    )
    (net (code "22") (name "Net-(JP23-Pad1)") (class "Default")
      (node (ref "JP23") (pin "1") (pinfunction "1_1") (pintype "passive"))
      (node (ref "JP23") (pin "2") (pinfunction "2_2") (pintype "passive"))
      (node (ref "JP23") (pin "3") (pinfunction "3_3") (pintype "passive"))
      (node (ref "JP23") (pin "4") (pinfunction "4_4") (pintype "passive"))
      (node (ref "JP23") (pin "5") (pinfunction "5_5") (pintype "passive"))
    )
    (net (code "23") (name "Net-(JP24-Pad1)") (class "Default")
      (node (ref "JP24") (pin "1") (pinfunction "1_1") (pintype "passive"))
      (node (ref "JP24") (pin "2") (pinfunction "2_2") (pintype "passive"))
      (node (ref "JP24") (pin "3") (pinfunction "3_3") (pintype "passive"))
      (node (ref "JP24") (pin "4") (pinfunction "4_4") (pintype "passive"))
      (node (ref "JP24") (pin "5") (pinfunction "5_5") (pintype "passive"))
    )
    (net (code "24") (name "Net-(JP25-Pad1)") (class "Default")
      (node (ref "JP25") (pin "1") (pinfunction "1_1") (pintype "passive"))
      (node (ref "JP25") (pin "2") (pinfunction "2_2") (pintype "passive"))
      (node (ref "JP25") (pin "3") (pinfunction "3_3") (pintype "passive"))
      (node (ref "JP25") (pin "4") (pinfunction "4_4") (pintype "passive"))
      (node (ref "JP25") (pin "5") (pinfunction "5_5") (pintype "passive"))
    )
    (net (code "25") (name "Net-(JP26-Pad1)") (class "Default")
      (node (ref "JP26") (pin "1") (pinfunction "1_1") (pintype "passive"))
      (node (ref "JP26") (pin "2") (pinfunction "2_2") (pintype "passive"))
      (node (ref "JP26") (pin "3") (pinfunction "3_3") (pintype "passive"))
      (node (ref "JP26") (pin "4") (pinfunction "4_4") (pintype "passive"))
      (node (ref "JP26") (pin "5") (pinfunction "5_5") (pintype "passive"))
    )
    (net (code "26") (name "Net-(JP27-Pad1)") (class "Default")
      (node (ref "JP27") (pin "1") (pinfunction "1_1") (pintype "passive"))
      (node (ref "JP27") (pin "2") (pinfunction "2_2") (pintype "passive"))
      (node (ref "JP27") (pin "3") (pinfunction "3_3") (pintype "passive"))
      (node (ref "JP27") (pin "4") (pinfunction "4_4") (pintype "passive"))
      (node (ref "JP27") (pin "5") (pinfunction "5_5") (pintype "passive"))
    )
    (net (code "27") (name "Net-(JP28-Pad1)") (class "Default")
      (node (ref "JP28") (pin "1") (pinfunction "1_1") (pintype "passive"))
      (node (ref "JP28") (pin "2") (pinfunction "2_2") (pintype "passive"))
      (node (ref "JP28") (pin "3") (pinfunction "3_3") (pintype "passive"))
      (node (ref "JP28") (pin "4") (pinfunction "4_4") (pintype "passive"))
      (node (ref "JP28") (pin "5") (pinfunction "5_5") (pintype "passive"))
    )
    (net (code "28") (name "Net-(JP29-Pad1)") (class "Default")
      (node (ref "JP29") (pin "1") (pinfunction "1_1") (pintype "passive"))
      (node (ref "JP29") (pin "2") (pinfunction "2_2") (pintype "passive"))
      (node (ref "JP29") (pin "3") (pinfunction "3_3") (pintype "passive"))
      (node (ref "JP29") (pin "4") (pinfunction "4_4") (pintype "passive"))
      (node (ref "JP29") (pin "5") (pinfunction "5_5") (pintype "passive"))
    )
    (net (code "29") (name "Net-(JP30-Pad1)") (class "Default")
      (node (ref "JP30") (pin "1") (pinfunction "1_1") (pintype "passive"))
      (node (ref "JP30") (pin "2") (pinfunction "2_2") (pintype "passive"))
      (node (ref "JP30") (pin "3") (pinfunction "3_3") (pintype "passive"))
      (node (ref "JP30") (pin "4") (pinfunction "4_4") (pintype "passive"))
      (node (ref "JP30") (pin "5") (pinfunction "5_5") (pintype "passive"))
    )
    (net (code "30") (name "Net-(JP31-Pad1)") (class "Default")
      (node (ref "JP31") (pin "1") (pinfunction "1_1") (pintype "passive"))
      (node (ref "JP31") (pin "2") (pinfunction "2_2") (pintype "passive"))
      (node (ref "JP31") (pin "3") (pinfunction "3_3") (pintype "passive"))
      (node (ref "JP31") (pin "4") (pinfunction "4_4") (pintype "passive"))
      (node (ref "JP31") (pin "5") (pinfunction "5_5") (pintype "passive"))
    )
    (net (code "31") (name "Net-(JP32-Pad1)") (class "Default")
      (node (ref "JP32") (pin "1") (pinfunction "1_1") (pintype "passive"))
      (node (ref "JP32") (pin "2") (pinfunction "2_2") (pintype "passive"))
      (node (ref "JP32") (pin "3") (pinfunction "3_3") (pintype "passive"))
      (node (ref "JP32") (pin "4") (pinfunction "4_4") (pintype "passive"))
      (node (ref "JP32") (pin "5") (pinfunction "5_5") (pintype "passive"))
    )
    (net (code "32") (name "Net-(JP33-Pad1)") (class "Default")
      (node (ref "JP33") (pin "1") (pinfunction "1_1") (pintype "passive"))
      (node (ref "JP33") (pin "2") (pinfunction "2_2") (pintype "passive"))
      (node (ref "JP33") (pin "3") (pinfunction "3_3") (pintype "passive"))
      (node (ref "JP33") (pin "4") (pinfunction "4_4") (pintype "passive"))
      (node (ref "JP33") (pin "5") (pinfunction "5_5") (pintype "passive"))
    )
    (net (code "33") (name "Net-(JP34-Pad1)") (class "Default")
      (node (ref "JP34") (pin "1") (pinfunction "1_1") (pintype "passive"))
      (node (ref "JP34") (pin "2") (pinfunction "2_2") (pintype "passive"))
      (node (ref "JP34") (pin "3") (pinfunction "3_3") (pintype "passive"))
      (node (ref "JP34") (pin "4") (pinfunction "4_4") (pintype "passive"))
      (node (ref "JP34") (pin "5") (pinfunction "5_5") (pintype "passive"))
    )
    (net (code "34") (name "Net-(JP35-Pad1)") (class "Default")
      (node (ref "JP35") (pin "1") (pinfunction "1_1") (pintype "passive"))
      (node (ref "JP35") (pin "2") (pinfunction "2_2") (pintype "passive"))
      (node (ref "JP35") (pin "3") (pinfunction "3_3") (pintype "passive"))
      (node (ref "JP35") (pin "4") (pinfunction "4_4") (pintype "passive"))
      (node (ref "JP35") (pin "5") (pinfunction "5_5") (pintype "passive"))
    )
    (net (code "35") (name "Net-(JP36-Pad1)") (class "Default")
      (node (ref "JP36") (pin "1") (pinfunction "1_1") (pintype "passive"))
      (node (ref "JP36") (pin "2") (pinfunction "2_2") (pintype "passive"))
      (node (ref "JP36") (pin "3") (pinfunction "3_3") (pintype "passive"))
      (node (ref "JP36") (pin "4") (pinfunction "4_4") (pintype "passive"))
      (node (ref "JP36") (pin "5") (pinfunction "5_5") (pintype "passive"))
    )
    (net (code "36") (name "Net-(JP37-Pad1)") (class "Default")
      (node (ref "JP37") (pin "1") (pinfunction "1_1") (pintype "passive"))
      (node (ref "JP37") (pin "2") (pinfunction "2_2") (pintype "passive"))
      (node (ref "JP37") (pin "3") (pinfunction "3_3") (pintype "passive"))
      (node (ref "JP37") (pin "4") (pinfunction "4_4") (pintype "passive"))
      (node (ref "JP37") (pin "5") (pinfunction "5_5") (pintype "passive"))
    )
    (net (code "37") (name "Net-(JP38-Pad1)") (class "Default")
      (node (ref "JP38") (pin "1") (pinfunction "1_1") (pintype "passive"))
      (node (ref "JP38") (pin "2") (pinfunction "2_2") (pintype "passive"))
      (node (ref "JP38") (pin "3") (pinfunction "3_3") (pintype "passive"))
      (node (ref "JP38") (pin "4") (pinfunction "4_4") (pintype "passive"))
      (node (ref "JP38") (pin "5") (pinfunction "5_5") (pintype "passive"))
    )
    (net (code "38") (name "Net-(JP39-Pad1)") (class "Default")
      (node (ref "JP39") (pin "1") (pinfunction "1_1") (pintype "passive"))
      (node (ref "JP39") (pin "2") (pinfunction "2_2") (pintype "passive"))
      (node (ref "JP39") (pin "3") (pinfunction "3_3") (pintype "passive"))
      (node (ref "JP39") (pin "4") (pinfunction "4_4") (pintype "passive"))
      (node (ref "JP39") (pin "5") (pinfunction "5_5") (pintype "passive"))
    )
    (net (code "39") (name "Net-(JP40-Pad1)") (class "Default")
      (node (ref "JP40") (pin "1") (pinfunction "1_1") (pintype "passive"))
      (node (ref "JP40") (pin "2") (pinfunction "2_2") (pintype "passive"))
      (node (ref "JP40") (pin "3") (pinfunction "3_3") (pintype "passive"))
      (node (ref "JP40") (pin "4") (pinfunction "4_4") (pintype "passive"))
      (node (ref "JP40") (pin "5") (pinfunction "5_5") (pintype "passive"))
    )
    (net (code "40") (name "Net-(JP41-Pad1)") (class "Default")
      (node (ref "JP41") (pin "1") (pinfunction "1_1") (pintype "passive"))
      (node (ref "JP41") (pin "2") (pinfunction "2_2") (pintype "passive"))
      (node (ref "JP41") (pin "3") (pinfunction "3_3") (pintype "passive"))
      (node (ref "JP41") (pin "4") (pinfunction "4_4") (pintype "passive"))
      (node (ref "JP41") (pin "5") (pinfunction "5_5") (pintype "passive"))
    )
    (net (code "41") (name "Net-(JP42-Pad1)") (class "Default")
      (node (ref "JP42") (pin "1") (pinfunction "1_1") (pintype "passive"))
      (node (ref "JP42") (pin "2") (pinfunction "2_2") (pintype "passive"))
      (node (ref "JP42") (pin "3") (pinfunction "3_3") (pintype "passive"))
      (node (ref "JP42") (pin "4") (pinfunction "4_4") (pintype "passive"))
      (node (ref "JP42") (pin "5") (pinfunction "5_5") (pintype "passive"))
    )
    (net (code "42") (name "Net-(JP43-Pad1)") (class "Default")
      (node (ref "JP43") (pin "1") (pinfunction "1_1") (pintype "passive"))
      (node (ref "JP43") (pin "2") (pinfunction "2_2") (pintype "passive"))
      (node (ref "JP43") (pin "3") (pinfunction "3_3") (pintype "passive"))
      (node (ref "JP43") (pin "4") (pinfunction "4_4") (pintype "passive"))
      (node (ref "JP43") (pin "5") (pinfunction "5_5") (pintype "passive"))
    )
    (net (code "43") (name "Net-(JP44-Pad1)") (class "Default")
      (node (ref "JP44") (pin "1") (pinfunction "1_1") (pintype "passive"))
      (node (ref "JP44") (pin "2") (pinfunction "2_2") (pintype "passive"))
      (node (ref "JP44") (pin "3") (pinfunction "3_3") (pintype "passive"))
      (node (ref "JP44") (pin "4") (pinfunction "4_4") (pintype "passive"))
      (node (ref "JP44") (pin "5") (pinfunction "5_5") (pintype "passive"))
    )
    (net (code "44") (name "Net-(JP45-Pad1)") (class "Default")
      (node (ref "JP45") (pin "1") (pinfunction "1_1") (pintype "passive"))
      (node (ref "JP45") (pin "2") (pinfunction "2_2") (pintype "passive"))
      (node (ref "JP45") (pin "3") (pinfunction "3_3") (pintype "passive"))
      (node (ref "JP45") (pin "4") (pinfunction "4_4") (pintype "passive"))
      (node (ref "JP45") (pin "5") (pinfunction "5_5") (pintype "passive"))
    )
    (net (code "45") (name "Net-(JP46-Pad1)") (class "Default")
      (node (ref "JP46") (pin "1") (pinfunction "1_1") (pintype "passive"))
      (node (ref "JP46") (pin "2") (pinfunction "2_2") (pintype "passive"))
      (node (ref "JP46") (pin "3") (pinfunction "3_3") (pintype "passive"))
      (node (ref "JP46") (pin "4") (pinfunction "4_4") (pintype "passive"))
      (node (ref "JP46") (pin "5") (pinfunction "5_5") (pintype "passive"))
    )
    (net (code "46") (name "Net-(JP47-Pad1)") (class "Default")
      (node (ref "JP47") (pin "1") (pinfunction "1_1") (pintype "passive"))
      (node (ref "JP47") (pin "2") (pinfunction "2_2") (pintype "passive"))
      (node (ref "JP47") (pin "3") (pinfunction "3_3") (pintype "passive"))
      (node (ref "JP47") (pin "4") (pinfunction "4_4") (pintype "passive"))
      (node (ref "JP47") (pin "5") (pinfunction "5_5") (pintype "passive"))
    )
    (net (code "47") (name "Net-(JP48-Pad1)") (class "Default")
      (node (ref "JP48") (pin "1") (pinfunction "1_1") (pintype "passive"))
      (node (ref "JP48") (pin "2") (pinfunction "2_2") (pintype "passive"))
      (node (ref "JP48") (pin "3") (pinfunction "3_3") (pintype "passive"))
      (node (ref "JP48") (pin "4") (pinfunction "4_4") (pintype "passive"))
      (node (ref "JP48") (pin "5") (pinfunction "5_5") (pintype "passive"))
    )
    (net (code "48") (name "Net-(JP49-Pad1)") (class "Default")
      (node (ref "JP49") (pin "1") (pinfunction "1_1") (pintype "passive"))
      (node (ref "JP49") (pin "2") (pinfunction "2_2") (pintype "passive"))
      (node (ref "JP49") (pin "3") (pinfunction "3_3") (pintype "passive"))
      (node (ref "JP49") (pin "4") (pinfunction "4_4") (pintype "passive"))
      (node (ref "JP49") (pin "5") (pinfunction "5_5") (pintype "passive"))
    )
    (net (code "49") (name "Net-(JP50-Pad1)") (class "Default")
      (node (ref "JP50") (pin "1") (pinfunction "1_1") (pintype "passive"))
      (node (ref "JP50") (pin "2") (pinfunction "2_2") (pintype "passive"))
      (node (ref "JP50") (pin "3") (pinfunction "3_3") (pintype "passive"))
      (node (ref "JP50") (pin "4") (pinfunction "4_4") (pintype "passive"))
      (node (ref "JP50") (pin "5") (pinfunction "5_5") (pintype "passive"))
    )
    (net (code "50") (name "Net-(JP51-Pad1)") (class "Default")
      (node (ref "JP51") (pin "1") (pinfunction "1_1") (pintype "passive"))
      (node (ref "JP51") (pin "2") (pinfunction "2_2") (pintype "passive"))
      (node (ref "JP51") (pin "3") (pinfunction "3_3") (pintype "passive"))
      (node (ref "JP51") (pin "4") (pinfunction "4_4") (pintype "passive"))
      (node (ref "JP51") (pin "5") (pinfunction "5_5") (pintype "passive"))
    )
    (net (code "51") (name "Net-(JP52-Pad1)") (class "Default")
      (node (ref "JP52") (pin "1") (pinfunction "1_1") (pintype "passive"))
      (node (ref "JP52") (pin "2") (pinfunction "2_2") (pintype "passive"))
      (node (ref "JP52") (pin "3") (pinfunction "3_3") (pintype "passive"))
      (node (ref "JP52") (pin "4") (pinfunction "4_4") (pintype "passive"))
      (node (ref "JP52") (pin "5") (pinfunction "5_5") (pintype "passive"))
    )
    (net (code "52") (name "Net-(JP53-Pad1)") (class "Default")
      (node (ref "JP53") (pin "1") (pinfunction "1_1") (pintype "passive"))
      (node (ref "JP53") (pin "2") (pinfunction "2_2") (pintype "passive"))
      (node (ref "JP53") (pin "3") (pinfunction "3_3") (pintype "passive"))
      (node (ref "JP53") (pin "4") (pinfunction "4_4") (pintype "passive"))
      (node (ref "JP53") (pin "5") (pinfunction "5_5") (pintype "passive"))
    )
    (net (code "53") (name "Net-(JP54-Pad1)") (class "Default")
      (node (ref "JP54") (pin "1") (pinfunction "1_1") (pintype "passive"))
      (node (ref "JP54") (pin "2") (pinfunction "2_2") (pintype "passive"))
      (node (ref "JP54") (pin "3") (pinfunction "3_3") (pintype "passive"))
      (node (ref "JP54") (pin "4") (pinfunction "4_4") (pintype "passive"))
      (node (ref "JP54") (pin "5") (pinfunction "5_5") (pintype "passive"))
    )
    (net (code "54") (name "Net-(JP55-Pad1)") (class "Default")
      (node (ref "JP55") (pin "1") (pinfunction "1_1") (pintype "passive"))
      (node (ref "JP55") (pin "2") (pinfunction "2_2") (pintype "passive"))
      (node (ref "JP55") (pin "3") (pinfunction "3_3") (pintype "passive"))
      (node (ref "JP55") (pin "4") (pinfunction "4_4") (pintype "passive"))
      (node (ref "JP55") (pin "5") (pinfunction "5_5") (pintype "passive"))
    )
    (net (code "55") (name "Net-(JP56-Pad1)") (class "Default")
      (node (ref "JP56") (pin "1") (pinfunction "1_1") (pintype "passive"))
      (node (ref "JP56") (pin "2") (pinfunction "2_2") (pintype "passive"))
      (node (ref "JP56") (pin "3") (pinfunction "3_3") (pintype "passive"))
      (node (ref "JP56") (pin "4") (pinfunction "4_4") (pintype "passive"))
      (node (ref "JP56") (pin "5") (pinfunction "5_5") (pintype "passive"))
    )
    (net (code "56") (name "Net-(JP57-Pad1)") (class "Default")
      (node (ref "JP57") (pin "1") (pinfunction "1_1") (pintype "passive"))
      (node (ref "JP57") (pin "2") (pinfunction "2_2") (pintype "passive"))
      (node (ref "JP57") (pin "3") (pinfunction "3_3") (pintype "passive"))
      (node (ref "JP57") (pin "4") (pinfunction "4_4") (pintype "passive"))
      (node (ref "JP57") (pin "5") (pinfunction "5_5") (pintype "passive"))
    )
    (net (code "57") (name "Net-(JP58-Pad1)") (class "Default")
      (node (ref "JP58") (pin "1") (pinfunction "1_1") (pintype "passive"))
      (node (ref "JP58") (pin "2") (pinfunction "2_2") (pintype "passive"))
      (node (ref "JP58") (pin "3") (pinfunction "3_3") (pintype "passive"))
      (node (ref "JP58") (pin "4") (pinfunction "4_4") (pintype "passive"))
      (node (ref "JP58") (pin "5") (pinfunction "5_5") (pintype "passive"))
    )
    (net (code "58") (name "Net-(JP59-Pad1)") (class "Default")
      (node (ref "JP59") (pin "1") (pinfunction "1_1") (pintype "passive"))
      (node (ref "JP59") (pin "2") (pinfunction "2_2") (pintype "passive"))
      (node (ref "JP59") (pin "3") (pinfunction "3_3") (pintype "passive"))
      (node (ref "JP59") (pin "4") (pinfunction "4_4") (pintype "passive"))
      (node (ref "JP59") (pin "5") (pinfunction "5_5") (pintype "passive"))
    )
    (net (code "59") (name "Net-(JP60-Pad1)") (class "Default")
      (node (ref "JP60") (pin "1") (pinfunction "1_1") (pintype "passive"))
      (node (ref "JP60") (pin "2") (pinfunction "2_2") (pintype "passive"))
      (node (ref "JP60") (pin "3") (pinfunction "3_3") (pintype "passive"))
      (node (ref "JP60") (pin "4") (pinfunction "4_4") (pintype "passive"))
      (node (ref "JP60") (pin "5") (pinfunction "5_5") (pintype "passive"))
    )
    (net (code "60") (name "Net-(JP61-Pad1)") (class "Default")
      (node (ref "JP61") (pin "1") (pinfunction "1_1") (pintype "passive"))
      (node (ref "JP61") (pin "2") (pinfunction "2_2") (pintype "passive"))
      (node (ref "JP61") (pin "3") (pinfunction "3_3") (pintype "passive"))
      (node (ref "JP61") (pin "4") (pinfunction "4_4") (pintype "passive"))
      (node (ref "JP61") (pin "5") (pinfunction "5_5") (pintype "passive"))
    )
    (net (code "61") (name "Net-(JP62-Pad1)") (class "Default")
      (node (ref "JP62") (pin "1") (pinfunction "1_1") (pintype "passive"))
      (node (ref "JP62") (pin "2") (pinfunction "2_2") (pintype "passive"))
      (node (ref "JP62") (pin "3") (pinfunction "3_3") (pintype "passive"))
      (node (ref "JP62") (pin "4") (pinfunction "4_4") (pintype "passive"))
      (node (ref "JP62") (pin "5") (pinfunction "5_5") (pintype "passive"))
    )
    (net (code "62") (name "Net-(JP63-Pad1)") (class "Default")
      (node (ref "JP63") (pin "1") (pinfunction "1_1") (pintype "passive"))
      (node (ref "JP63") (pin "2") (pinfunction "2_2") (pintype "passive"))
      (node (ref "JP63") (pin "3") (pinfunction "3_3") (pintype "passive"))
      (node (ref "JP63") (pin "4") (pinfunction "4_4") (pintype "passive"))
      (node (ref "JP63") (pin "5") (pinfunction "5_5") (pintype "passive"))
    )
    (net (code "63") (name "Net-(JP64-Pad1)") (class "Default")
      (node (ref "JP64") (pin "1") (pinfunction "1_1") (pintype "passive"))
      (node (ref "JP64") (pin "2") (pinfunction "2_2") (pintype "passive"))
      (node (ref "JP64") (pin "3") (pinfunction "3_3") (pintype "passive"))
      (node (ref "JP64") (pin "4") (pinfunction "4_4") (pintype "passive"))
      (node (ref "JP64") (pin "5") (pinfunction "5_5") (pintype "passive"))
    )
    (net (code "64") (name "Net-(JP69-Pad1)") (class "Default")
      (node (ref "JP69") (pin "1") (pinfunction "1_1") (pintype "passive"))
      (node (ref "JP69") (pin "2") (pinfunction "2_2") (pintype "passive"))
      (node (ref "JP69") (pin "3") (pinfunction "3_3") (pintype "passive"))
      (node (ref "JP69") (pin "4") (pinfunction "4_4") (pintype "passive"))
      (node (ref "JP69") (pin "5") (pinfunction "5_5") (pintype "passive"))
    )
    (net (code "65") (name "Net-(JP70-Pad1)") (class "Default")
      (node (ref "JP70") (pin "1") (pinfunction "1_1") (pintype "passive"))
      (node (ref "JP70") (pin "2") (pinfunction "2_2") (pintype "passive"))
      (node (ref "JP70") (pin "3") (pinfunction "3_3") (pintype "passive"))
      (node (ref "JP70") (pin "4") (pinfunction "4_4") (pintype "passive"))
      (node (ref "JP70") (pin "5") (pinfunction "5_5") (pintype "passive"))
    )
    (net (code "66") (name "Net-(JP71-Pad1)") (class "Default")
      (node (ref "JP71") (pin "1") (pinfunction "1_1") (pintype "passive"))
      (node (ref "JP71") (pin "2") (pinfunction "2_2") (pintype "passive"))
      (node (ref "JP71") (pin "3") (pinfunction "3_3") (pintype "passive"))
      (node (ref "JP71") (pin "4") (pinfunction "4_4") (pintype "passive"))
      (node (ref "JP71") (pin "5") (pinfunction "5_5") (pintype "passive"))
    )
    (net (code "67") (name "Net-(JP72-Pad1)") (class "Default")
      (node (ref "JP72") (pin "1") (pinfunction "1_1") (pintype "passive"))
      (node (ref "JP72") (pin "2") (pinfunction "2_2") (pintype "passive"))
      (node (ref "JP72") (pin "3") (pinfunction "3_3") (pintype "passive"))
      (node (ref "JP72") (pin "4") (pinfunction "4_4") (pintype "passive"))
      (node (ref "JP72") (pin "5") (pinfunction "5_5") (pintype "passive"))
    )
    (net (code "68") (name "Net-(JP73-Pad1)") (class "Default")
      (node (ref "JP73") (pin "1") (pinfunction "1_1") (pintype "passive"))
      (node (ref "JP73") (pin "2") (pinfunction "2_2") (pintype "passive"))
      (node (ref "JP73") (pin "3") (pinfunction "3_3") (pintype "passive"))
      (node (ref "JP73") (pin "4") (pinfunction "4_4") (pintype "passive"))
      (node (ref "JP73") (pin "5") (pinfunction "5_5") (pintype "passive"))
    )
    (net (code "69") (name "Net-(JP74-Pad1)") (class "Default")
      (node (ref "JP74") (pin "1") (pinfunction "1_1") (pintype "passive"))
      (node (ref "JP74") (pin "2") (pinfunction "2_2") (pintype "passive"))
      (node (ref "JP74") (pin "3") (pinfunction "3_3") (pintype "passive"))
      (node (ref "JP74") (pin "4") (pinfunction "4_4") (pintype "passive"))
      (node (ref "JP74") (pin "5") (pinfunction "5_5") (pintype "passive"))
    )
    (net (code "70") (name "Net-(JP75-Pad1)") (class "Default")
      (node (ref "JP75") (pin "1") (pinfunction "1_1") (pintype "passive"))
      (node (ref "JP75") (pin "2") (pinfunction "2_2") (pintype "passive"))
      (node (ref "JP75") (pin "3") (pinfunction "3_3") (pintype "passive"))
      (node (ref "JP75") (pin "4") (pinfunction "4_4") (pintype "passive"))
      (node (ref "JP75") (pin "5") (pinfunction "5_5") (pintype "passive"))
    )
    (net (code "71") (name "Net-(JP76-Pad1)") (class "Default")
      (node (ref "JP76") (pin "1") (pinfunction "1_1") (pintype "passive"))
      (node (ref "JP76") (pin "2") (pinfunction "2_2") (pintype "passive"))
      (node (ref "JP76") (pin "3") (pinfunction "3_3") (pintype "passive"))
      (node (ref "JP76") (pin "4") (pinfunction "4_4") (pintype "passive"))
      (node (ref "JP76") (pin "5") (pinfunction "5_5") (pintype "passive"))
    )
    (net (code "72") (name "Net-(JP77-Pad1)") (class "Default")
      (node (ref "JP77") (pin "1") (pinfunction "1_1") (pintype "passive"))
      (node (ref "JP77") (pin "2") (pinfunction "2_2") (pintype "passive"))
      (node (ref "JP77") (pin "3") (pinfunction "3_3") (pintype "passive"))
      (node (ref "JP77") (pin "4") (pinfunction "4_4") (pintype "passive"))
      (node (ref "JP77") (pin "5") (pinfunction "5_5") (pintype "passive"))
    )
    (net (code "73") (name "Net-(JP78-Pad1)") (class "Default")
      (node (ref "JP78") (pin "1") (pinfunction "1_1") (pintype "passive"))
      (node (ref "JP78") (pin "2") (pinfunction "2_2") (pintype "passive"))
      (node (ref "JP78") (pin "3") (pinfunction "3_3") (pintype "passive"))
      (node (ref "JP78") (pin "4") (pinfunction "4_4") (pintype "passive"))
      (node (ref "JP78") (pin "5") (pinfunction "5_5") (pintype "passive"))
    )
    (net (code "74") (name "Net-(JP79-Pad1)") (class "Default")
      (node (ref "JP79") (pin "1") (pinfunction "1_1") (pintype "passive"))
      (node (ref "JP79") (pin "2") (pinfunction "2_2") (pintype "passive"))
      (node (ref "JP79") (pin "3") (pinfunction "3_3") (pintype "passive"))
      (node (ref "JP79") (pin "4") (pinfunction "4_4") (pintype "passive"))
      (node (ref "JP79") (pin "5") (pinfunction "5_5") (pintype "passive"))
    )
    (net (code "75") (name "Net-(JP80-Pad1)") (class "Default")
      (node (ref "JP80") (pin "1") (pinfunction "1_1") (pintype "passive"))
      (node (ref "JP80") (pin "2") (pinfunction "2_2") (pintype "passive"))
      (node (ref "JP80") (pin "3") (pinfunction "3_3") (pintype "passive"))
      (node (ref "JP80") (pin "4") (pinfunction "4_4") (pintype "passive"))
      (node (ref "JP80") (pin "5") (pinfunction "5_5") (pintype "passive"))
    )
    (net (code "76") (name "Net-(JP81-Pad1)") (class "Default")
      (node (ref "JP81") (pin "1") (pinfunction "1_1") (pintype "passive"))
      (node (ref "JP81") (pin "2") (pinfunction "2_2") (pintype "passive"))
      (node (ref "JP81") (pin "3") (pinfunction "3_3") (pintype "passive"))
      (node (ref "JP81") (pin "4") (pinfunction "4_4") (pintype "passive"))
      (node (ref "JP81") (pin "5") (pinfunction "5_5") (pintype "passive"))
    )
    (net (code "77") (name "Net-(JP82-Pad1)") (class "Default")
      (node (ref "JP82") (pin "1") (pinfunction "1_1") (pintype "passive"))
      (node (ref "JP82") (pin "2") (pinfunction "2_2") (pintype "passive"))
      (node (ref "JP82") (pin "3") (pinfunction "3_3") (pintype "passive"))
      (node (ref "JP82") (pin "4") (pinfunction "4_4") (pintype "passive"))
      (node (ref "JP82") (pin "5") (pinfunction "5_5") (pintype "passive"))
    )
    (net (code "78") (name "Net-(JP83-Pad1)") (class "Default")
      (node (ref "JP83") (pin "1") (pinfunction "1_1") (pintype "passive"))
      (node (ref "JP83") (pin "2") (pinfunction "2_2") (pintype "passive"))
      (node (ref "JP83") (pin "3") (pinfunction "3_3") (pintype "passive"))
      (node (ref "JP83") (pin "4") (pinfunction "4_4") (pintype "passive"))
      (node (ref "JP83") (pin "5") (pinfunction "5_5") (pintype "passive"))
    )
    (net (code "79") (name "Net-(JP84-Pad1)") (class "Default")
      (node (ref "JP84") (pin "1") (pinfunction "1_1") (pintype "passive"))
      (node (ref "JP84") (pin "2") (pinfunction "2_2") (pintype "passive"))
      (node (ref "JP84") (pin "3") (pinfunction "3_3") (pintype "passive"))
      (node (ref "JP84") (pin "4") (pinfunction "4_4") (pintype "passive"))
      (node (ref "JP84") (pin "5") (pinfunction "5_5") (pintype "passive"))
    )
    (net (code "80") (name "Net-(JP85-Pad1)") (class "Default")
      (node (ref "JP85") (pin "1") (pinfunction "1_1") (pintype "passive"))
      (node (ref "JP85") (pin "2") (pinfunction "2_2") (pintype "passive"))
      (node (ref "JP85") (pin "3") (pinfunction "3_3") (pintype "passive"))
      (node (ref "JP85") (pin "4") (pinfunction "4_4") (pintype "passive"))
      (node (ref "JP85") (pin "5") (pinfunction "5_5") (pintype "passive"))
    )
    (net (code "81") (name "Net-(JP86-Pad1)") (class "Default")
      (node (ref "JP86") (pin "1") (pinfunction "1_1") (pintype "passive"))
      (node (ref "JP86") (pin "2") (pinfunction "2_2") (pintype "passive"))
      (node (ref "JP86") (pin "3") (pinfunction "3_3") (pintype "passive"))
      (node (ref "JP86") (pin "4") (pinfunction "4_4") (pintype "passive"))
      (node (ref "JP86") (pin "5") (pinfunction "5_5") (pintype "passive"))
    )
    (net (code "82") (name "Net-(JP87-Pad1)") (class "Default")
      (node (ref "JP87") (pin "1") (pinfunction "1_1") (pintype "passive"))
      (node (ref "JP87") (pin "2") (pinfunction "2_2") (pintype "passive"))
      (node (ref "JP87") (pin "3") (pinfunction "3_3") (pintype "passive"))
      (node (ref "JP87") (pin "4") (pinfunction "4_4") (pintype "passive"))
      (node (ref "JP87") (pin "5") (pinfunction "5_5") (pintype "passive"))
    )
    (net (code "83") (name "Net-(JP88-Pad1)") (class "Default")
      (node (ref "JP88") (pin "1") (pinfunction "1_1") (pintype "passive"))
      (node (ref "JP88") (pin "2") (pinfunction "2_2") (pintype "passive"))
      (node (ref "JP88") (pin "3") (pinfunction "3_3") (pintype "passive"))
      (node (ref "JP88") (pin "4") (pinfunction "4_4") (pintype "passive"))
      (node (ref "JP88") (pin "5") (pinfunction "5_5") (pintype "passive"))
    )
    (net (code "84") (name "Net-(JP89-Pad1)") (class "Default")
      (node (ref "JP89") (pin "1") (pinfunction "1_1") (pintype "passive"))
      (node (ref "JP89") (pin "2") (pinfunction "2_2") (pintype "passive"))
      (node (ref "JP89") (pin "3") (pinfunction "3_3") (pintype "passive"))
      (node (ref "JP89") (pin "4") (pinfunction "4_4") (pintype "passive"))
      (node (ref "JP89") (pin "5") (pinfunction "5_5") (pintype "passive"))
    )
    (net (code "85") (name "Net-(JP90-Pad1)") (class "Default")
      (node (ref "JP90") (pin "1") (pinfunction "1_1") (pintype "passive"))
      (node (ref "JP90") (pin "2") (pinfunction "2_2") (pintype "passive"))
      (node (ref "JP90") (pin "3") (pinfunction "3_3") (pintype "passive"))
      (node (ref "JP90") (pin "4") (pinfunction "4_4") (pintype "passive"))
      (node (ref "JP90") (pin "5") (pinfunction "5_5") (pintype "passive"))
    )
    (net (code "86") (name "Net-(JP91-Pad1)") (class "Default")
      (node (ref "JP91") (pin "1") (pinfunction "1_1") (pintype "passive"))
      (node (ref "JP91") (pin "2") (pinfunction "2_2") (pintype "passive"))
      (node (ref "JP91") (pin "3") (pinfunction "3_3") (pintype "passive"))
      (node (ref "JP91") (pin "4") (pinfunction "4_4") (pintype "passive"))
      (node (ref "JP91") (pin "5") (pinfunction "5_5") (pintype "passive"))
    )
    (net (code "87") (name "Net-(JP92-Pad1)") (class "Default")
      (node (ref "JP92") (pin "1") (pinfunction "1_1") (pintype "passive"))
      (node (ref "JP92") (pin "2") (pinfunction "2_2") (pintype "passive"))
      (node (ref "JP92") (pin "3") (pinfunction "3_3") (pintype "passive"))
      (node (ref "JP92") (pin "4") (pinfunction "4_4") (pintype "passive"))
      (node (ref "JP92") (pin "5") (pinfunction "5_5") (pintype "passive"))
    )
    (net (code "88") (name "Net-(JP93-Pad1)") (class "Default")
      (node (ref "JP93") (pin "1") (pinfunction "1_1") (pintype "passive"))
      (node (ref "JP93") (pin "2") (pinfunction "2_2") (pintype "passive"))
      (node (ref "JP93") (pin "3") (pinfunction "3_3") (pintype "passive"))
      (node (ref "JP93") (pin "4") (pinfunction "4_4") (pintype "passive"))
      (node (ref "JP93") (pin "5") (pinfunction "5_5") (pintype "passive"))
    )
    (net (code "89") (name "Net-(JP94-Pad1)") (class "Default")
      (node (ref "JP94") (pin "1") (pinfunction "1_1") (pintype "passive"))
      (node (ref "JP94") (pin "2") (pinfunction "2_2") (pintype "passive"))
      (node (ref "JP94") (pin "3") (pinfunction "3_3") (pintype "passive"))
      (node (ref "JP94") (pin "4") (pinfunction "4_4") (pintype "passive"))
      (node (ref "JP94") (pin "5") (pinfunction "5_5") (pintype "passive"))
    )
    (net (code "90") (name "Net-(JP95-Pad1)") (class "Default")
      (node (ref "JP95") (pin "1") (pinfunction "1_1") (pintype "passive"))
      (node (ref "JP95") (pin "2") (pinfunction "2_2") (pintype "passive"))
      (node (ref "JP95") (pin "3") (pinfunction "3_3") (pintype "passive"))
      (node (ref "JP95") (pin "4") (pinfunction "4_4") (pintype "passive"))
      (node (ref "JP95") (pin "5") (pinfunction "5_5") (pintype "passive"))
    )
    (net (code "91") (name "Net-(JP96-Pad1)") (class "Default")
      (node (ref "JP96") (pin "1") (pinfunction "1_1") (pintype "passive"))
      (node (ref "JP96") (pin "2") (pinfunction "2_2") (pintype "passive"))
      (node (ref "JP96") (pin "3") (pinfunction "3_3") (pintype "passive"))
      (node (ref "JP96") (pin "4") (pinfunction "4_4") (pintype "passive"))
      (node (ref "JP96") (pin "5") (pinfunction "5_5") (pintype "passive"))
    )
    (net (code "92") (name "Net-(JP97-Pad1)") (class "Default")
      (node (ref "JP97") (pin "1") (pinfunction "1_1") (pintype "passive"))
      (node (ref "JP97") (pin "2") (pinfunction "2_2") (pintype "passive"))
      (node (ref "JP97") (pin "3") (pinfunction "3_3") (pintype "passive"))
      (node (ref "JP97") (pin "4") (pinfunction "4_4") (pintype "passive"))
      (node (ref "JP97") (pin "5") (pinfunction "5_5") (pintype "passive"))
    )
    (net (code "93") (name "Net-(JP98-Pad1)") (class "Default")
      (node (ref "JP98") (pin "1") (pinfunction "1_1") (pintype "passive"))
      (node (ref "JP98") (pin "2") (pinfunction "2_2") (pintype "passive"))
      (node (ref "JP98") (pin "3") (pinfunction "3_3") (pintype "passive"))
      (node (ref "JP98") (pin "4") (pinfunction "4_4") (pintype "passive"))
      (node (ref "JP98") (pin "5") (pinfunction "5_5") (pintype "passive"))
    )
    (net (code "94") (name "Net-(JP99-Pad1)") (class "Default")
      (node (ref "JP99") (pin "1") (pinfunction "1_1") (pintype "passive"))
      (node (ref "JP99") (pin "2") (pinfunction "2_2") (pintype "passive"))
      (node (ref "JP99") (pin "3") (pinfunction "3_3") (pintype "passive"))
      (node (ref "JP99") (pin "4") (pinfunction "4_4") (pintype "passive"))
      (node (ref "JP99") (pin "5") (pinfunction "5_5") (pintype "passive"))
    )
    (net (code "95") (name "Net-(JP100-Pad1)") (class "Default")
      (node (ref "JP100") (pin "1") (pinfunction "1_1") (pintype "passive"))
      (node (ref "JP100") (pin "2") (pinfunction "2_2") (pintype "passive"))
      (node (ref "JP100") (pin "3") (pinfunction "3_3") (pintype "passive"))
      (node (ref "JP100") (pin "4") (pinfunction "4_4") (pintype "passive"))
      (node (ref "JP100") (pin "5") (pinfunction "5_5") (pintype "passive"))
    )
    (net (code "96") (name "Net-(JP101-Pad1)") (class "Default")
      (node (ref "JP101") (pin "1") (pinfunction "1_1") (pintype "passive"))
      (node (ref "JP101") (pin "2") (pinfunction "2_2") (pintype "passive"))
      (node (ref "JP101") (pin "3") (pinfunction "3_3") (pintype "passive"))
      (node (ref "JP101") (pin "4") (pinfunction "4_4") (pintype "passive"))
      (node (ref "JP101") (pin "5") (pinfunction "5_5") (pintype "passive"))
    )
    (net (code "97") (name "Net-(JP102-Pad1)") (class "Default")
      (node (ref "JP102") (pin "1") (pinfunction "1_1") (pintype "passive"))
      (node (ref "JP102") (pin "2") (pinfunction "2_2") (pintype "passive"))
      (node (ref "JP102") (pin "3") (pinfunction "3_3") (pintype "passive"))
      (node (ref "JP102") (pin "4") (pinfunction "4_4") (pintype "passive"))
      (node (ref "JP102") (pin "5") (pinfunction "5_5") (pintype "passive"))
    )
    (net (code "98") (name "Net-(JP103-Pad1)") (class "Default")
      (node (ref "JP103") (pin "1") (pinfunction "1_1") (pintype "passive"))
      (node (ref "JP103") (pin "2") (pinfunction "2_2") (pintype "passive"))
      (node (ref "JP103") (pin "3") (pinfunction "3_3") (pintype "passive"))
      (node (ref "JP103") (pin "4") (pinfunction "4_4") (pintype "passive"))
      (node (ref "JP103") (pin "5") (pinfunction "5_5") (pintype "passive"))
    )
    (net (code "99") (name "Net-(JP104-Pad1)") (class "Default")
      (node (ref "JP104") (pin "1") (pinfunction "1_1") (pintype "passive"))
      (node (ref "JP104") (pin "2") (pinfunction "2_2") (pintype "passive"))
      (node (ref "JP104") (pin "3") (pinfunction "3_3") (pintype "passive"))
      (node (ref "JP104") (pin "4") (pinfunction "4_4") (pintype "passive"))
      (node (ref "JP104") (pin "5") (pinfunction "5_5") (pintype "passive"))
    )
    (net (code "100") (name "Net-(JP105-Pad1)") (class "Default")
      (node (ref "JP105") (pin "1") (pinfunction "1_1") (pintype "passive"))
      (node (ref "JP105") (pin "2") (pinfunction "2_2") (pintype "passive"))
      (node (ref "JP105") (pin "3") (pinfunction "3_3") (pintype "passive"))
      (node (ref "JP105") (pin "4") (pinfunction "4_4") (pintype "passive"))
      (node (ref "JP105") (pin "5") (pinfunction "5_5") (pintype "passive"))
    )
    (net (code "101") (name "Net-(JP106-Pad1)") (class "Default")
      (node (ref "JP106") (pin "1") (pinfunction "1_1") (pintype "passive"))
      (node (ref "JP106") (pin "2") (pinfunction "2_2") (pintype "passive"))
      (node (ref "JP106") (pin "3") (pinfunction "3_3") (pintype "passive"))
      (node (ref "JP106") (pin "4") (pinfunction "4_4") (pintype "passive"))
      (node (ref "JP106") (pin "5") (pinfunction "5_5") (pintype "passive"))
    )
    (net (code "102") (name "Net-(JP107-Pad1)") (class "Default")
      (node (ref "JP107") (pin "1") (pinfunction "1_1") (pintype "passive"))
      (node (ref "JP107") (pin "2") (pinfunction "2_2") (pintype "passive"))
      (node (ref "JP107") (pin "3") (pinfunction "3_3") (pintype "passive"))
      (node (ref "JP107") (pin "4") (pinfunction "4_4") (pintype "passive"))
      (node (ref "JP107") (pin "5") (pinfunction "5_5") (pintype "passive"))
    )
    (net (code "103") (name "Net-(JP108-Pad1)") (class "Default")
      (node (ref "JP108") (pin "1") (pinfunction "1_1") (pintype "passive"))
      (node (ref "JP108") (pin "2") (pinfunction "2_2") (pintype "passive"))
      (node (ref "JP108") (pin "3") (pinfunction "3_3") (pintype "passive"))
      (node (ref "JP108") (pin "4") (pinfunction "4_4") (pintype "passive"))
      (node (ref "JP108") (pin "5") (pinfunction "5_5") (pintype "passive"))
    )
    (net (code "104") (name "Net-(JP109-Pad1)") (class "Default")
      (node (ref "JP109") (pin "1") (pinfunction "1_1") (pintype "passive"))
      (node (ref "JP109") (pin "2") (pinfunction "2_2") (pintype "passive"))
      (node (ref "JP109") (pin "3") (pinfunction "3_3") (pintype "passive"))
      (node (ref "JP109") (pin "4") (pinfunction "4_4") (pintype "passive"))
      (node (ref "JP109") (pin "5") (pinfunction "5_5") (pintype "passive"))
    )
    (net (code "105") (name "Net-(JP110-Pad1)") (class "Default")
      (node (ref "JP110") (pin "1") (pinfunction "1_1") (pintype "passive"))
      (node (ref "JP110") (pin "2") (pinfunction "2_2") (pintype "passive"))
      (node (ref "JP110") (pin "3") (pinfunction "3_3") (pintype "passive"))
      (node (ref "JP110") (pin "4") (pinfunction "4_4") (pintype "passive"))
      (node (ref "JP110") (pin "5") (pinfunction "5_5") (pintype "passive"))
    )
    (net (code "106") (name "Net-(JP111-Pad1)") (class "Default")
      (node (ref "JP111") (pin "1") (pinfunction "1_1") (pintype "passive"))
      (node (ref "JP111") (pin "2") (pinfunction "2_2") (pintype "passive"))
      (node (ref "JP111") (pin "3") (pinfunction "3_3") (pintype "passive"))
      (node (ref "JP111") (pin "4") (pinfunction "4_4") (pintype "passive"))
      (node (ref "JP111") (pin "5") (pinfunction "5_5") (pintype "passive"))
    )
    (net (code "107") (name "Net-(JP112-Pad1)") (class "Default")
      (node (ref "JP112") (pin "1") (pinfunction "1_1") (pintype "passive"))
      (node (ref "JP112") (pin "2") (pinfunction "2_2") (pintype "passive"))
      (node (ref "JP112") (pin "3") (pinfunction "3_3") (pintype "passive"))
      (node (ref "JP112") (pin "4") (pinfunction "4_4") (pintype "passive"))
      (node (ref "JP112") (pin "5") (pinfunction "5_5") (pintype "passive"))
    )
    (net (code "108") (name "Net-(JP113-Pad1)") (class "Default")
      (node (ref "JP113") (pin "1") (pinfunction "1_1") (pintype "passive"))
      (node (ref "JP113") (pin "2") (pinfunction "2_2") (pintype "passive"))
      (node (ref "JP113") (pin "3") (pinfunction "3_3") (pintype "passive"))
      (node (ref "JP113") (pin "4") (pinfunction "4_4") (pintype "passive"))
      (node (ref "JP113") (pin "5") (pinfunction "5_5") (pintype "passive"))
    )
    (net (code "109") (name "Net-(JP114-Pad1)") (class "Default")
      (node (ref "JP114") (pin "1") (pinfunction "1_1") (pintype "passive"))
      (node (ref "JP114") (pin "2") (pinfunction "2_2") (pintype "passive"))
      (node (ref "JP114") (pin "3") (pinfunction "3_3") (pintype "passive"))
      (node (ref "JP114") (pin "4") (pinfunction "4_4") (pintype "passive"))
      (node (ref "JP114") (pin "5") (pinfunction "5_5") (pintype "passive"))
    )
    (net (code "110") (name "Net-(JP115-Pad1)") (class "Default")
      (node (ref "JP115") (pin "1") (pinfunction "1_1") (pintype "passive"))
      (node (ref "JP115") (pin "2") (pinfunction "2_2") (pintype "passive"))
      (node (ref "JP115") (pin "3") (pinfunction "3_3") (pintype "passive"))
      (node (ref "JP115") (pin "4") (pinfunction "4_4") (pintype "passive"))
      (node (ref "JP115") (pin "5") (pinfunction "5_5") (pintype "passive"))
    )
    (net (code "111") (name "Net-(JP116-Pad1)") (class "Default")
      (node (ref "JP116") (pin "1") (pinfunction "1_1") (pintype "passive"))
      (node (ref "JP116") (pin "2") (pinfunction "2_2") (pintype "passive"))
      (node (ref "JP116") (pin "3") (pinfunction "3_3") (pintype "passive"))
      (node (ref "JP116") (pin "4") (pinfunction "4_4") (pintype "passive"))
      (node (ref "JP116") (pin "5") (pinfunction "5_5") (pintype "passive"))
    )
    (net (code "112") (name "Net-(JP117-Pad1)") (class "Default")
      (node (ref "JP117") (pin "1") (pinfunction "1_1") (pintype "passive"))
      (node (ref "JP117") (pin "2") (pinfunction "2_2") (pintype "passive"))
      (node (ref "JP117") (pin "3") (pinfunction "3_3") (pintype "passive"))
      (node (ref "JP117") (pin "4") (pinfunction "4_4") (pintype "passive"))
      (node (ref "JP117") (pin "5") (pinfunction "5_5") (pintype "passive"))
    )
    (net (code "113") (name "Net-(JP118-Pad1)") (class "Default")
      (node (ref "JP118") (pin "1") (pinfunction "1_1") (pintype "passive"))
      (node (ref "JP118") (pin "2") (pinfunction "2_2") (pintype "passive"))
      (node (ref "JP118") (pin "3") (pinfunction "3_3") (pintype "passive"))
      (node (ref "JP118") (pin "4") (pinfunction "4_4") (pintype "passive"))
      (node (ref "JP118") (pin "5") (pinfunction "5_5") (pintype "passive"))
    )
    (net (code "114") (name "Net-(JP119-Pad1)") (class "Default")
      (node (ref "JP119") (pin "1") (pinfunction "1_1") (pintype "passive"))
      (node (ref "JP119") (pin "2") (pinfunction "2_2") (pintype "passive"))
      (node (ref "JP119") (pin "3") (pinfunction "3_3") (pintype "passive"))
      (node (ref "JP119") (pin "4") (pinfunction "4_4") (pintype "passive"))
      (node (ref "JP119") (pin "5") (pinfunction "5_5") (pintype "passive"))
    )
    (net (code "115") (name "Net-(JP120-Pad1)") (class "Default")
      (node (ref "JP120") (pin "1") (pinfunction "1_1") (pintype "passive"))
      (node (ref "JP120") (pin "2") (pinfunction "2_2") (pintype "passive"))
      (node (ref "JP120") (pin "3") (pinfunction "3_3") (pintype "passive"))
      (node (ref "JP120") (pin "4") (pinfunction "4_4") (pintype "passive"))
      (node (ref "JP120") (pin "5") (pinfunction "5_5") (pintype "passive"))
    )
    (net (code "116") (name "Net-(JP121-Pad1)") (class "Default")
      (node (ref "JP121") (pin "1") (pinfunction "1_1") (pintype "passive"))
      (node (ref "JP121") (pin "2") (pinfunction "2_2") (pintype "passive"))
      (node (ref "JP121") (pin "3") (pinfunction "3_3") (pintype "passive"))
      (node (ref "JP121") (pin "4") (pinfunction "4_4") (pintype "passive"))
      (node (ref "JP121") (pin "5") (pinfunction "5_5") (pintype "passive"))
    )
    (net (code "117") (name "Net-(JP122-Pad1)") (class "Default")
      (node (ref "JP122") (pin "1") (pinfunction "1_1") (pintype "passive"))
      (node (ref "JP122") (pin "2") (pinfunction "2_2") (pintype "passive"))
      (node (ref "JP122") (pin "3") (pinfunction "3_3") (pintype "passive"))
      (node (ref "JP122") (pin "4") (pinfunction "4_4") (pintype "passive"))
      (node (ref "JP122") (pin "5") (pinfunction "5_5") (pintype "passive"))
    )
    (net (code "118") (name "Net-(JP123-Pad1)") (class "Default")
      (node (ref "JP123") (pin "1") (pinfunction "1_1") (pintype "passive"))
      (node (ref "JP123") (pin "2") (pinfunction "2_2") (pintype "passive"))
      (node (ref "JP123") (pin "3") (pinfunction "3_3") (pintype "passive"))
      (node (ref "JP123") (pin "4") (pinfunction "4_4") (pintype "passive"))
      (node (ref "JP123") (pin "5") (pinfunction "5_5") (pintype "passive"))
    )
    (net (code "119") (name "Net-(JP124-Pad1)") (class "Default")
      (node (ref "JP124") (pin "1") (pinfunction "1_1") (pintype "passive"))
      (node (ref "JP124") (pin "2") (pinfunction "2_2") (pintype "passive"))
      (node (ref "JP124") (pin "3") (pinfunction "3_3") (pintype "passive"))
      (node (ref "JP124") (pin "4") (pinfunction "4_4") (pintype "passive"))
      (node (ref "JP124") (pin "5") (pinfunction "5_5") (pintype "passive"))
    )
    (net (code "120") (name "Net-(JP125-Pad1)") (class "Default")
      (node (ref "JP125") (pin "1") (pinfunction "1_1") (pintype "passive"))
      (node (ref "JP125") (pin "2") (pinfunction "2_2") (pintype "passive"))
      (node (ref "JP125") (pin "3") (pinfunction "3_3") (pintype "passive"))
      (node (ref "JP125") (pin "4") (pinfunction "4_4") (pintype "passive"))
      (node (ref "JP125") (pin "5") (pinfunction "5_5") (pintype "passive"))
    )
    (net (code "121") (name "Net-(JP126-Pad1)") (class "Default")
      (node (ref "JP126") (pin "1") (pinfunction "1_1") (pintype "passive"))
      (node (ref "JP126") (pin "2") (pinfunction "2_2") (pintype "passive"))
      (node (ref "JP126") (pin "3") (pinfunction "3_3") (pintype "passive"))
      (node (ref "JP126") (pin "4") (pinfunction "4_4") (pintype "passive"))
      (node (ref "JP126") (pin "5") (pinfunction "5_5") (pintype "passive"))
    )
    (net (code "122") (name "Net-(JP127-Pad1)") (class "Default")
      (node (ref "JP127") (pin "1") (pinfunction "1_1") (pintype "passive"))
      (node (ref "JP127") (pin "2") (pinfunction "2_2") (pintype "passive"))
      (node (ref "JP127") (pin "3") (pinfunction "3_3") (pintype "passive"))
      (node (ref "JP127") (pin "4") (pinfunction "4_4") (pintype "passive"))
      (node (ref "JP127") (pin "5") (pinfunction "5_5") (pintype "passive"))
    )
    (net (code "123") (name "Net-(JP128-Pad1)") (class "Default")
      (node (ref "JP128") (pin "1") (pinfunction "1_1") (pintype "passive"))
      (node (ref "JP128") (pin "2") (pinfunction "2_2") (pintype "passive"))
      (node (ref "JP128") (pin "3") (pinfunction "3_3") (pintype "passive"))
      (node (ref "JP128") (pin "4") (pinfunction "4_4") (pintype "passive"))
      (node (ref "JP128") (pin "5") (pinfunction "5_5") (pintype "passive"))
    )
    (net (code "124") (name "Net-(JP130-Pad1)") (class "Default")
      (node (ref "JP130") (pin "1") (pinfunction "1_1") (pintype "passive"))
      (node (ref "JP130") (pin "10") (pinfunction "10_10") (pintype "passive"))
      (node (ref "JP130") (pin "11") (pinfunction "11_11") (pintype "passive"))
      (node (ref "JP130") (pin "12") (pinfunction "12_12") (pintype "passive"))
      (node (ref "JP130") (pin "13") (pinfunction "13_13") (pintype "passive"))
      (node (ref "JP130") (pin "14") (pinfunction "14_14") (pintype "passive"))
      (node (ref "JP130") (pin "15") (pinfunction "15_15") (pintype "passive"))
      (node (ref "JP130") (pin "16") (pinfunction "16_16") (pintype "passive"))
      (node (ref "JP130") (pin "17") (pinfunction "17_17") (pintype "passive"))
      (node (ref "JP130") (pin "18") (pinfunction "18_18") (pintype "passive"))
      (node (ref "JP130") (pin "19") (pinfunction "19_19") (pintype "passive"))
      (node (ref "JP130") (pin "2") (pinfunction "2_2") (pintype "passive"))
      (node (ref "JP130") (pin "20") (pinfunction "20_20") (pintype "passive"))
      (node (ref "JP130") (pin "21") (pinfunction "21_21") (pintype "passive"))
      (node (ref "JP130") (pin "22") (pinfunction "22_22") (pintype "passive"))
      (node (ref "JP130") (pin "23") (pinfunction "23_23") (pintype "passive"))
      (node (ref "JP130") (pin "24") (pinfunction "24_24") (pintype "passive"))
      (node (ref "JP130") (pin "25") (pinfunction "25_25") (pintype "passive"))
      (node (ref "JP130") (pin "26") (pinfunction "26_26") (pintype "passive"))
      (node (ref "JP130") (pin "27") (pinfunction "27_27") (pintype "passive"))
      (node (ref "JP130") (pin "28") (pinfunction "28_28") (pintype "passive"))
      (node (ref "JP130") (pin "29") (pinfunction "29_29") (pintype "passive"))
      (node (ref "JP130") (pin "3") (pinfunction "3_3") (pintype "passive"))
      (node (ref "JP130") (pin "4") (pinfunction "4_4") (pintype "passive"))
      (node (ref "JP130") (pin "5") (pinfunction "5_5") (pintype "passive"))
      (node (ref "JP130") (pin "6") (pinfunction "6_6") (pintype "passive"))
      (node (ref "JP130") (pin "7") (pinfunction "7_7") (pintype "passive"))
      (node (ref "JP130") (pin "8") (pinfunction "8_8") (pintype "passive"))
      (node (ref "JP130") (pin "9") (pinfunction "9_9") (pintype "passive"))
      (node (ref "JP131") (pin "1") (pinfunction "1_1") (pintype "passive"))
      (node (ref "JP131") (pin "2") (pinfunction "2_2") (pintype "passive"))
      (node (ref "JP131") (pin "3") (pinfunction "3_3") (pintype "passive"))
      (node (ref "JP131") (pin "4") (pinfunction "4_4") (pintype "passive"))
      (node (ref "JP131") (pin "5") (pinfunction "5_5") (pintype "passive"))
      (node (ref "JP146") (pin "2") (pinfunction "2_2") (pintype "passive"))
      (node (ref "JP148") (pin "2") (pinfunction "2_2") (pintype "passive"))
      (node (ref "JP2") (pin "1") (pinfunction "1_1") (pintype "passive"))
      (node (ref "JP2") (pin "10") (pinfunction "10_10") (pintype "passive"))
      (node (ref "JP2") (pin "11") (pinfunction "11_11") (pintype "passive"))
      (node (ref "JP2") (pin "12") (pinfunction "12_12") (pintype "passive"))
      (node (ref "JP2") (pin "13") (pinfunction "13_13") (pintype "passive"))
      (node (ref "JP2") (pin "14") (pinfunction "14_14") (pintype "passive"))
      (node (ref "JP2") (pin "15") (pinfunction "15_15") (pintype "passive"))
      (node (ref "JP2") (pin "16") (pinfunction "16_16") (pintype "passive"))
      (node (ref "JP2") (pin "17") (pinfunction "17_17") (pintype "passive"))
      (node (ref "JP2") (pin "18") (pinfunction "18_18") (pintype "passive"))
      (node (ref "JP2") (pin "19") (pinfunction "19_19") (pintype "passive"))
      (node (ref "JP2") (pin "2") (pinfunction "2_2") (pintype "passive"))
      (node (ref "JP2") (pin "20") (pinfunction "20_20") (pintype "passive"))
      (node (ref "JP2") (pin "21") (pinfunction "21_21") (pintype "passive"))
      (node (ref "JP2") (pin "22") (pinfunction "22_22") (pintype "passive"))
      (node (ref "JP2") (pin "23") (pinfunction "23_23") (pintype "passive"))
      (node (ref "JP2") (pin "24") (pinfunction "24_24") (pintype "passive"))
      (node (ref "JP2") (pin "25") (pinfunction "25_25") (pintype "passive"))
      (node (ref "JP2") (pin "26") (pinfunction "26_26") (pintype "passive"))
      (node (ref "JP2") (pin "27") (pinfunction "27_27") (pintype "passive"))
      (node (ref "JP2") (pin "28") (pinfunction "28_28") (pintype "passive"))
      (node (ref "JP2") (pin "29") (pinfunction "29_29") (pintype "passive"))
      (node (ref "JP2") (pin "3") (pinfunction "3_3") (pintype "passive"))
      (node (ref "JP2") (pin "4") (pinfunction "4_4") (pintype "passive"))
      (node (ref "JP2") (pin "5") (pinfunction "5_5") (pintype "passive"))
      (node (ref "JP2") (pin "6") (pinfunction "6_6") (pintype "passive"))
      (node (ref "JP2") (pin "7") (pinfunction "7_7") (pintype "passive"))
      (node (ref "JP2") (pin "8") (pinfunction "8_8") (pintype "passive"))
      (node (ref "JP2") (pin "9") (pinfunction "9_9") (pintype "passive"))
      (node (ref "TIE+1") (pin "1") (pinfunction "1_1") (pintype "passive"))
    )
    (net (code "125") (name "Net-(JP134-Pad1)") (class "Default")
      (node (ref "JP134") (pin "1") (pinfunction "1_1") (pintype "passive"))
      (node (ref "JP134") (pin "10") (pinfunction "10_10") (pintype "passive"))
      (node (ref "JP134") (pin "11") (pinfunction "11_11") (pintype "passive"))
      (node (ref "JP134") (pin "12") (pinfunction "12_12") (pintype "passive"))
      (node (ref "JP134") (pin "13") (pinfunction "13_13") (pintype "passive"))
      (node (ref "JP134") (pin "14") (pinfunction "14_14") (pintype "passive"))
      (node (ref "JP134") (pin "15") (pinfunction "15_15") (pintype "passive"))
      (node (ref "JP134") (pin "16") (pinfunction "16_16") (pintype "passive"))
      (node (ref "JP134") (pin "17") (pinfunction "17_17") (pintype "passive"))
      (node (ref "JP134") (pin "18") (pinfunction "18_18") (pintype "passive"))
      (node (ref "JP134") (pin "19") (pinfunction "19_19") (pintype "passive"))
      (node (ref "JP134") (pin "2") (pinfunction "2_2") (pintype "passive"))
      (node (ref "JP134") (pin "20") (pinfunction "20_20") (pintype "passive"))
      (node (ref "JP134") (pin "21") (pinfunction "21_21") (pintype "passive"))
      (node (ref "JP134") (pin "22") (pinfunction "22_22") (pintype "passive"))
      (node (ref "JP134") (pin "23") (pinfunction "23_23") (pintype "passive"))
      (node (ref "JP134") (pin "24") (pinfunction "24_24") (pintype "passive"))
      (node (ref "JP134") (pin "25") (pinfunction "25_25") (pintype "passive"))
      (node (ref "JP134") (pin "26") (pinfunction "26_26") (pintype "passive"))
      (node (ref "JP134") (pin "27") (pinfunction "27_27") (pintype "passive"))
      (node (ref "JP134") (pin "28") (pinfunction "28_28") (pintype "passive"))
      (node (ref "JP134") (pin "29") (pinfunction "29_29") (pintype "passive"))
      (node (ref "JP134") (pin "3") (pinfunction "3_3") (pintype "passive"))
      (node (ref "JP134") (pin "4") (pinfunction "4_4") (pintype "passive"))
      (node (ref "JP134") (pin "5") (pinfunction "5_5") (pintype "passive"))
      (node (ref "JP134") (pin "6") (pinfunction "6_6") (pintype "passive"))
      (node (ref "JP134") (pin "7") (pinfunction "7_7") (pintype "passive"))
      (node (ref "JP134") (pin "8") (pinfunction "8_8") (pintype "passive"))
      (node (ref "JP134") (pin "9") (pinfunction "9_9") (pintype "passive"))
      (node (ref "JP135") (pin "1") (pinfunction "1_1") (pintype "passive"))
      (node (ref "JP135") (pin "2") (pinfunction "2_2") (pintype "passive"))
      (node (ref "JP135") (pin "3") (pinfunction "3_3") (pintype "passive"))
      (node (ref "JP135") (pin "4") (pinfunction "4_4") (pintype "passive"))
      (node (ref "JP135") (pin "5") (pinfunction "5_5") (pintype "passive"))
      (node (ref "JP147") (pin "3") (pinfunction "3_3") (pintype "passive"))
      (node (ref "JP149") (pin "1") (pinfunction "1_1") (pintype "passive"))
      (node (ref "JP4") (pin "1") (pinfunction "1_1") (pintype "passive"))
      (node (ref "JP4") (pin "10") (pinfunction "10_10") (pintype "passive"))
      (node (ref "JP4") (pin "11") (pinfunction "11_11") (pintype "passive"))
      (node (ref "JP4") (pin "12") (pinfunction "12_12") (pintype "passive"))
      (node (ref "JP4") (pin "13") (pinfunction "13_13") (pintype "passive"))
      (node (ref "JP4") (pin "14") (pinfunction "14_14") (pintype "passive"))
      (node (ref "JP4") (pin "15") (pinfunction "15_15") (pintype "passive"))
      (node (ref "JP4") (pin "16") (pinfunction "16_16") (pintype "passive"))
      (node (ref "JP4") (pin "17") (pinfunction "17_17") (pintype "passive"))
      (node (ref "JP4") (pin "18") (pinfunction "18_18") (pintype "passive"))
      (node (ref "JP4") (pin "19") (pinfunction "19_19") (pintype "passive"))
      (node (ref "JP4") (pin "2") (pinfunction "2_2") (pintype "passive"))
      (node (ref "JP4") (pin "20") (pinfunction "20_20") (pintype "passive"))
      (node (ref "JP4") (pin "21") (pinfunction "21_21") (pintype "passive"))
      (node (ref "JP4") (pin "22") (pinfunction "22_22") (pintype "passive"))
      (node (ref "JP4") (pin "23") (pinfunction "23_23") (pintype "passive"))
      (node (ref "JP4") (pin "24") (pinfunction "24_24") (pintype "passive"))
      (node (ref "JP4") (pin "25") (pinfunction "25_25") (pintype "passive"))
      (node (ref "JP4") (pin "26") (pinfunction "26_26") (pintype "passive"))
      (node (ref "JP4") (pin "27") (pinfunction "27_27") (pintype "passive"))
      (node (ref "JP4") (pin "28") (pinfunction "28_28") (pintype "passive"))
      (node (ref "JP4") (pin "29") (pinfunction "29_29") (pintype "passive"))
      (node (ref "JP4") (pin "3") (pinfunction "3_3") (pintype "passive"))
      (node (ref "JP4") (pin "4") (pinfunction "4_4") (pintype "passive"))
      (node (ref "JP4") (pin "5") (pinfunction "5_5") (pintype "passive"))
      (node (ref "JP4") (pin "6") (pinfunction "6_6") (pintype "passive"))
      (node (ref "JP4") (pin "7") (pinfunction "7_7") (pintype "passive"))
      (node (ref "JP4") (pin "8") (pinfunction "8_8") (pintype "passive"))
      (node (ref "JP4") (pin "9") (pinfunction "9_9") (pintype "passive"))
      (node (ref "TIE+2") (pin "1") (pinfunction "1_1") (pintype "passive"))
    )
    (net (code "126") (name "Net-(JP140-Pad1)") (class "Default")
      (node (ref "JP140") (pin "1") (pinfunction "1_1") (pintype "passive"))
      (node (ref "JP140") (pin "2") (pinfunction "2_2") (pintype "passive"))
      (node (ref "JP140") (pin "3") (pinfunction "3_3") (pintype "passive"))
      (node (ref "JP140") (pin "4") (pinfunction "4_4") (pintype "passive"))
      (node (ref "JP140") (pin "5") (pinfunction "5_5") (pintype "passive"))
    )
    (net (code "127") (name "Net-(JP141-Pad1)") (class "Default")
      (node (ref "JP141") (pin "1") (pinfunction "1_1") (pintype "passive"))
      (node (ref "JP141") (pin "2") (pinfunction "2_2") (pintype "passive"))
      (node (ref "JP141") (pin "3") (pinfunction "3_3") (pintype "passive"))
      (node (ref "JP141") (pin "4") (pinfunction "4_4") (pintype "passive"))
      (node (ref "JP141") (pin "5") (pinfunction "5_5") (pintype "passive"))
    )
    (net (code "128") (name "Net-(JP142-Pad1)") (class "Default")
      (node (ref "JP142") (pin "1") (pinfunction "1_1") (pintype "passive"))
      (node (ref "JP142") (pin "2") (pinfunction "2_2") (pintype "passive"))
      (node (ref "JP142") (pin "3") (pinfunction "3_3") (pintype "passive"))
      (node (ref "JP142") (pin "4") (pinfunction "4_4") (pintype "passive"))
      (node (ref "JP142") (pin "5") (pinfunction "5_5") (pintype "passive"))
    )
    (net (code "129") (name "Net-(JP143-Pad1)") (class "Default")
      (node (ref "JP143") (pin "1") (pinfunction "1_1") (pintype "passive"))
      (node (ref "JP143") (pin "2") (pinfunction "2_2") (pintype "passive"))
      (node (ref "JP143") (pin "3") (pinfunction "3_3") (pintype "passive"))
      (node (ref "JP143") (pin "4") (pinfunction "4_4") (pintype "passive"))
      (node (ref "JP143") (pin "5") (pinfunction "5_5") (pintype "passive"))
    )
    (net (code "130") (name "Net-(JP144-Pad1)") (class "Default")
      (node (ref "JP144") (pin "1") (pinfunction "1_1") (pintype "passive"))
      (node (ref "JP144") (pin "2") (pinfunction "2_2") (pintype "passive"))
      (node (ref "JP144") (pin "3") (pinfunction "3_3") (pintype "passive"))
      (node (ref "JP144") (pin "4") (pinfunction "4_4") (pintype "passive"))
      (node (ref "JP144") (pin "5") (pinfunction "5_5") (pintype "passive"))
    )
    (net (code "131") (name "Net-(JP145-Pad1)") (class "Default")
      (node (ref "JP145") (pin "1") (pinfunction "1_1") (pintype "passive"))
      (node (ref "JP145") (pin "2") (pinfunction "2_2") (pintype "passive"))
      (node (ref "JP145") (pin "3") (pinfunction "3_3") (pintype "passive"))
      (node (ref "JP145") (pin "4") (pinfunction "4_4") (pintype "passive"))
      (node (ref "JP145") (pin "5") (pinfunction "5_5") (pintype "passive"))
    )
    (net (code "132") (name "Net-(S1-P$1)") (class "Default")
      (node (ref "JG1") (pin "2") (pinfunction "2_2") (pintype "passive"))
      (node (ref "S1") (pin "P1") (pinfunction "P$1_P1") (pintype "bidirectional"))
    )
    (net (code "133") (name "Net-(S2-P$1)") (class "Default")
      (node (ref "JG2") (pin "2") (pinfunction "2_2") (pintype "passive"))
      (node (ref "S2") (pin "P1") (pinfunction "P$1_P1") (pintype "bidirectional"))
    )
    (net (code "134") (name "Net-(S3-P$1)") (class "Default")
      (node (ref "JG3") (pin "1") (pinfunction "1_1") (pintype "passive"))
      (node (ref "S3") (pin "P1") (pinfunction "P$1_P1") (pintype "bidirectional"))
    )
    (net (code "135") (name "Net-(S4-P$1)") (class "Default")
      (node (ref "JG4") (pin "1") (pinfunction "1_1") (pintype "passive"))
      (node (ref "S4") (pin "P1") (pinfunction "P$1_P1") (pintype "bidirectional"))
    )
  )
)
